# HashUnit1.net
KiCad netlist of a schematic drawn in Altium Designer
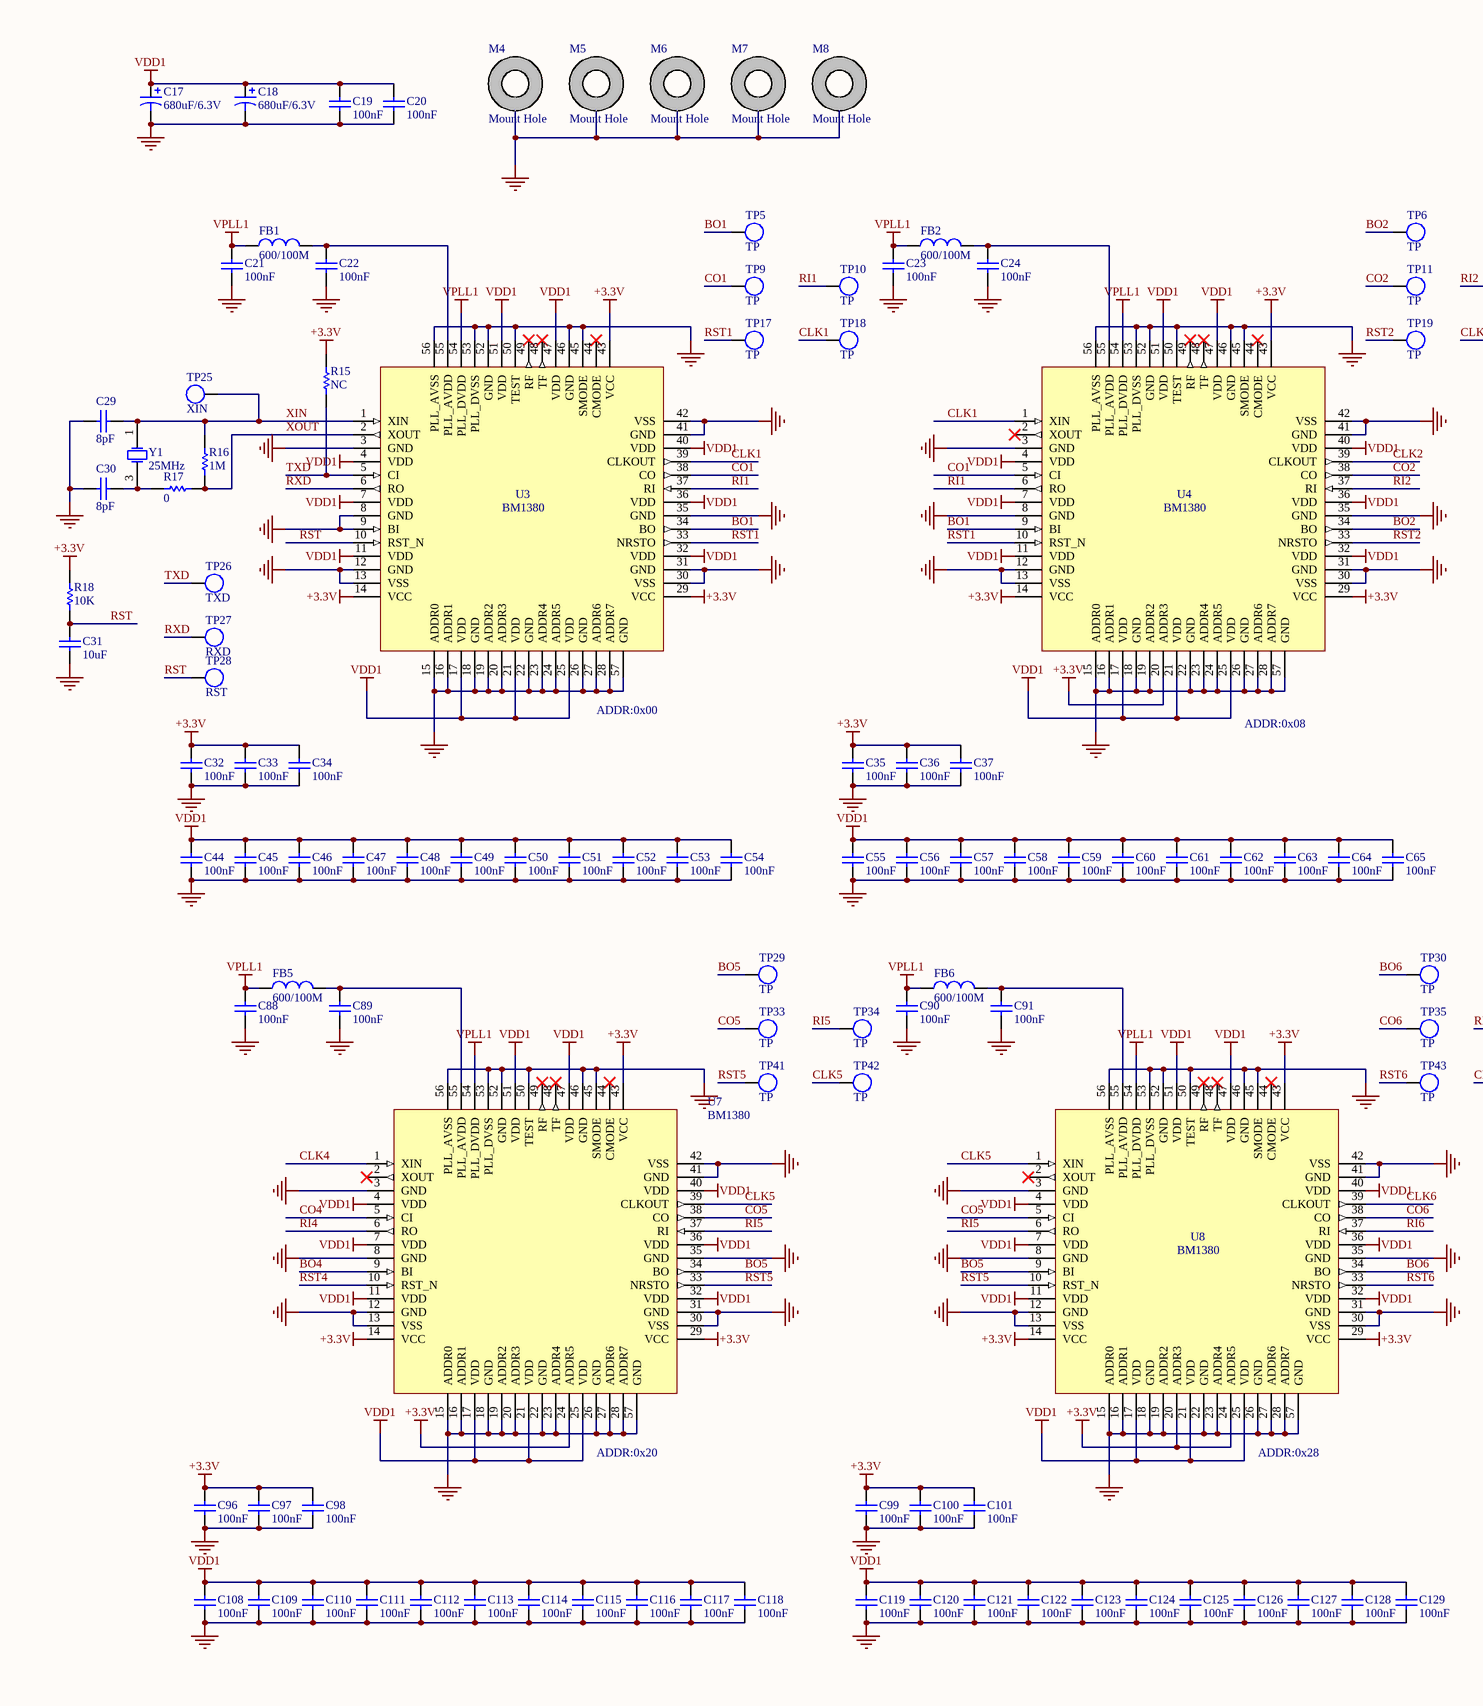
[diagram p0: HashUnit1.SchDoc, left]
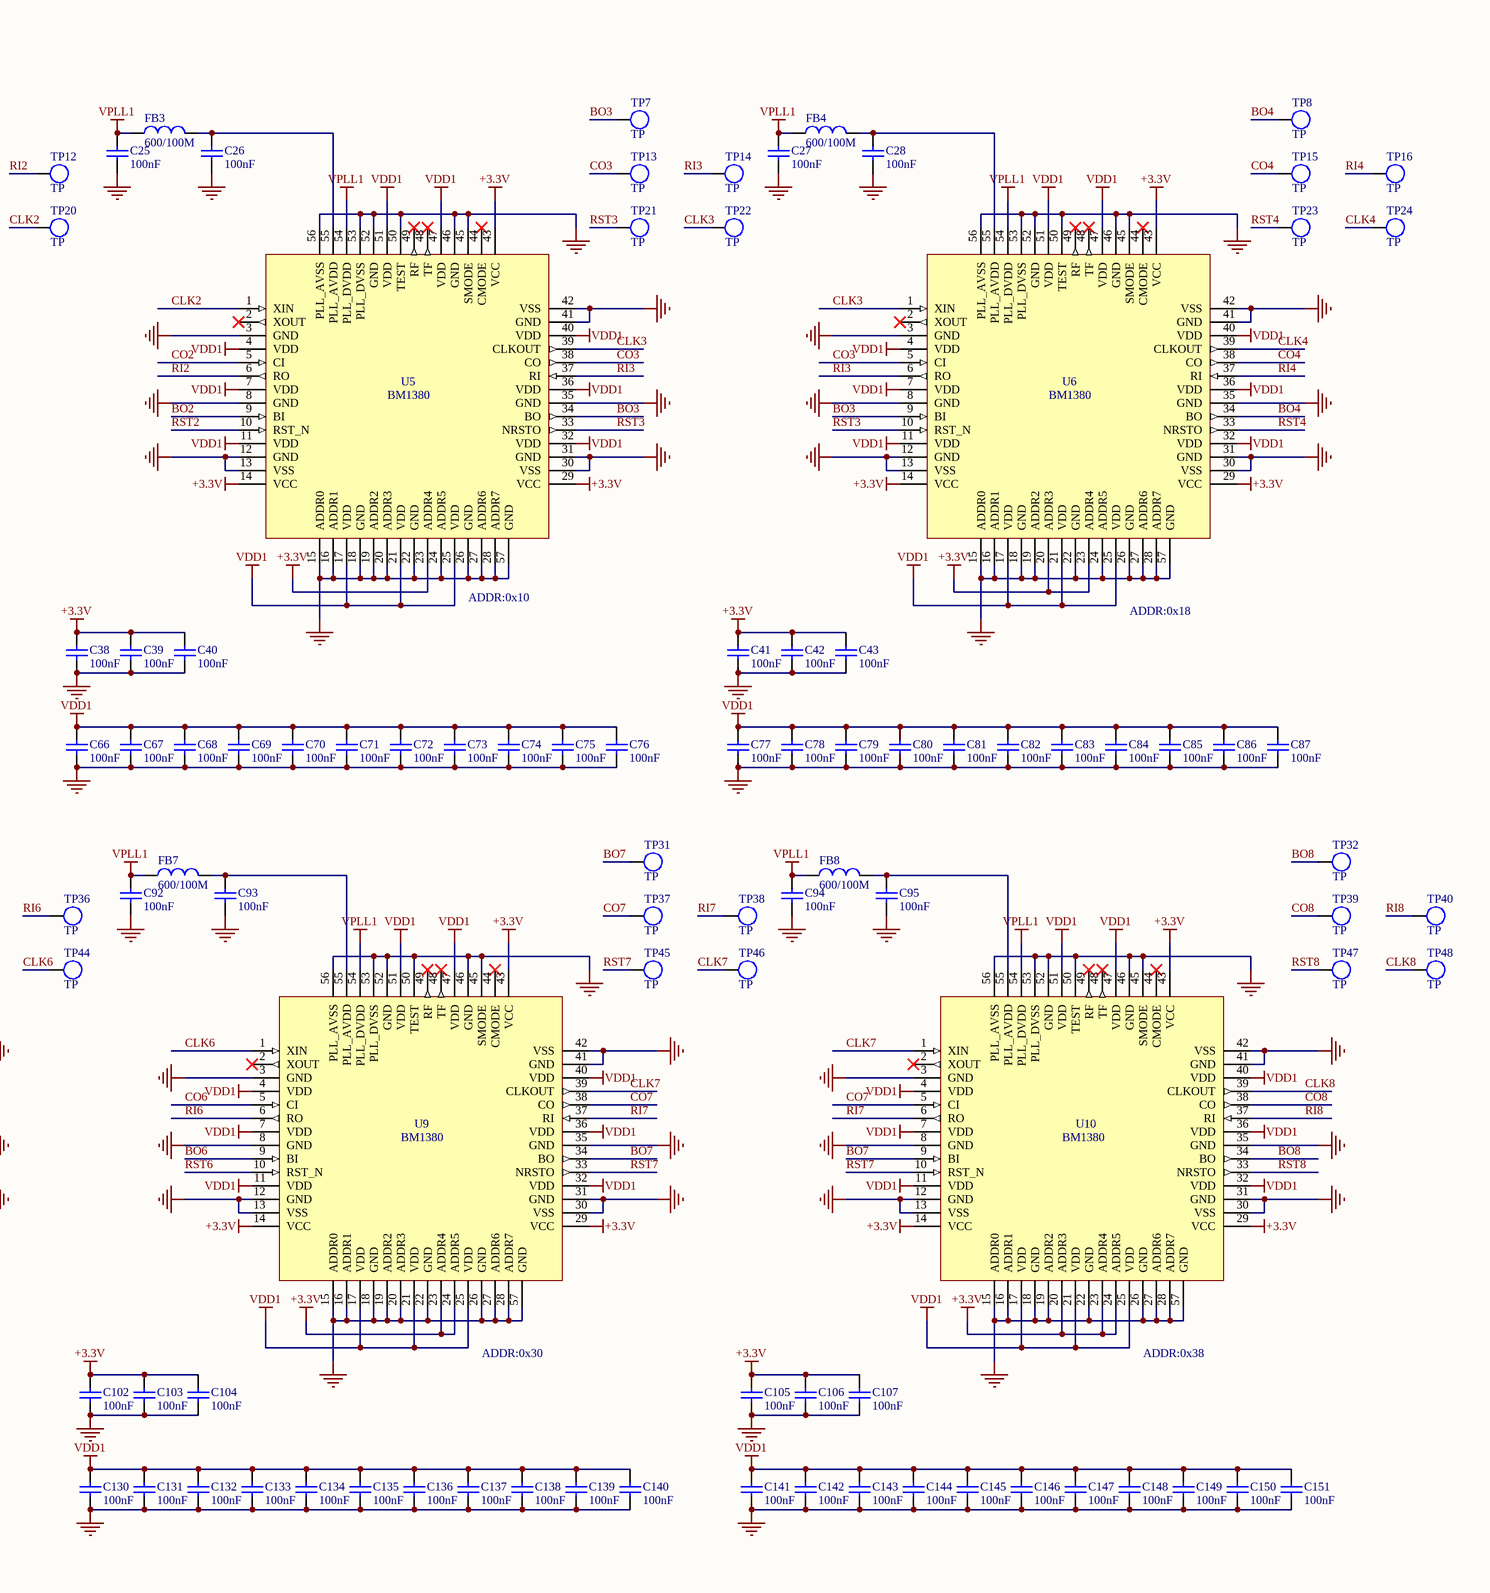
[diagram p1: HashUnit1.SchDoc, right]

(export (version "E")
  (design (tool "Eeschema 10.0.6"))
  (components
    (comp (ref "C17")
      (value "680uF/6.3V")
      (footprint "D")
      (description "Solid Tantalum Chip Capacitor, T492 Series - CWR11 Style Per Mil-PRF-55365/8")
      (fields (field (name "PUBLISHER") "Altium Limited"))
      (libsource (lib "KEMET Chip Capacitor") (part "T492C"))
    )
    (comp (ref "C18")
      (value "680uF/6.3V")
      (footprint "D")
      (description "Solid Tantalum Chip Capacitor, T492 Series - CWR11 Style Per Mil-PRF-55365/8")
      (fields (field (name "PUBLISHER") "Altium Limited"))
      (libsource (lib "KEMET Chip Capacitor") (part "T492C"))
    )
    (comp (ref "C19")
      (value "100nF")
      (footprint "CC0603(1608)")
      (description "Capacitor (Semiconductor SIM Model)")
      (fields (field (name "PUBLISHER") "Altium Limited"))
      (libsource (lib "Miscellaneous Devices") (part "Cap Semi"))
    )
    (comp (ref "C20")
      (value "100nF")
      (footprint "CC0603(1608)")
      (description "Capacitor (Semiconductor SIM Model)")
      (fields (field (name "PUBLISHER") "Altium Limited"))
      (libsource (lib "Miscellaneous Devices") (part "Cap Semi"))
    )
    (comp (ref "C21")
      (value "100nF")
      (footprint "CC0603(1608)")
      (description "Capacitor")
      (fields (field (name "PUBLISHER") "Altium Limited"))
      (libsource (lib "BitMain_Miner_1") (part "Cap"))
    )
    (comp (ref "C22")
      (value "100nF")
      (footprint "CC0603(1608)")
      (description "Capacitor")
      (fields (field (name "PUBLISHER") "Altium Limited"))
      (libsource (lib "BitMain_Miner_1") (part "Cap"))
    )
    (comp (ref "C23")
      (value "100nF")
      (footprint "CC0603(1608)")
      (description "Capacitor")
      (fields (field (name "PUBLISHER") "Altium Limited"))
      (libsource (lib "BitMain_Miner_1") (part "Cap"))
    )
    (comp (ref "C24")
      (value "100nF")
      (footprint "CC0603(1608)")
      (description "Capacitor")
      (fields (field (name "PUBLISHER") "Altium Limited"))
      (libsource (lib "BitMain_Miner_1") (part "Cap"))
    )
    (comp (ref "C25")
      (value "100nF")
      (footprint "CC0603(1608)")
      (description "Capacitor")
      (fields (field (name "PUBLISHER") "Altium Limited"))
      (libsource (lib "BitMain_Miner_1") (part "Cap"))
    )
    (comp (ref "C26")
      (value "100nF")
      (footprint "CC0603(1608)")
      (description "Capacitor")
      (fields (field (name "PUBLISHER") "Altium Limited"))
      (libsource (lib "BitMain_Miner_1") (part "Cap"))
    )
    (comp (ref "C27")
      (value "100nF")
      (footprint "CC0603(1608)")
      (description "Capacitor")
      (fields (field (name "PUBLISHER") "Altium Limited"))
      (libsource (lib "BitMain_Miner_1") (part "Cap"))
    )
    (comp (ref "C28")
      (value "100nF")
      (footprint "CC0603(1608)")
      (description "Capacitor")
      (fields (field (name "PUBLISHER") "Altium Limited"))
      (libsource (lib "BitMain_Miner_1") (part "Cap"))
    )
    (comp (ref "C29")
      (value "8pF")
      (footprint "CC0603(1608)")
      (description "Capacitor")
      (fields (field (name "PUBLISHER") "Altium Limited"))
      (libsource (lib "BitMain_Miner_1") (part "Cap"))
    )
    (comp (ref "C30")
      (value "8pF")
      (footprint "CC0603(1608)")
      (description "Capacitor")
      (fields (field (name "PUBLISHER") "Altium Limited"))
      (libsource (lib "BitMain_Miner_1") (part "Cap"))
    )
    (comp (ref "C31")
      (value "10uF")
      (footprint "CC0603(1608)")
      (description "Capacitor")
      (fields (field (name "PUBLISHER") "Altium Limited"))
      (libsource (lib "BitMain_Miner_1") (part "Cap"))
    )
    (comp (ref "C32")
      (value "100nF")
      (footprint "CC0603(1608)")
      (description "Capacitor")
      (fields (field (name "PUBLISHER") "Altium Limited"))
      (libsource (lib "BitMain_Miner_1") (part "Cap"))
    )
    (comp (ref "C33")
      (value "100nF")
      (footprint "CC0603(1608)")
      (description "Capacitor")
      (fields (field (name "PUBLISHER") "Altium Limited"))
      (libsource (lib "BitMain_Miner_1") (part "Cap"))
    )
    (comp (ref "C34")
      (value "100nF")
      (footprint "CC0603(1608)")
      (description "Capacitor")
      (fields (field (name "PUBLISHER") "Altium Limited"))
      (libsource (lib "BitMain_Miner_1") (part "Cap"))
    )
    (comp (ref "C35")
      (value "100nF")
      (footprint "CC0603(1608)")
      (description "Capacitor")
      (fields (field (name "PUBLISHER") "Altium Limited"))
      (libsource (lib "BitMain_Miner_1") (part "Cap"))
    )
    (comp (ref "C36")
      (value "100nF")
      (footprint "CC0603(1608)")
      (description "Capacitor")
      (fields (field (name "PUBLISHER") "Altium Limited"))
      (libsource (lib "BitMain_Miner_1") (part "Cap"))
    )
    (comp (ref "C37")
      (value "100nF")
      (footprint "CC0603(1608)")
      (description "Capacitor")
      (fields (field (name "PUBLISHER") "Altium Limited"))
      (libsource (lib "BitMain_Miner_1") (part "Cap"))
    )
    (comp (ref "C38")
      (value "100nF")
      (footprint "CC0603(1608)")
      (description "Capacitor")
      (fields (field (name "PUBLISHER") "Altium Limited"))
      (libsource (lib "BitMain_Miner_1") (part "Cap"))
    )
    (comp (ref "C39")
      (value "100nF")
      (footprint "CC0603(1608)")
      (description "Capacitor")
      (fields (field (name "PUBLISHER") "Altium Limited"))
      (libsource (lib "BitMain_Miner_1") (part "Cap"))
    )
    (comp (ref "C40")
      (value "100nF")
      (footprint "CC0603(1608)")
      (description "Capacitor")
      (fields (field (name "PUBLISHER") "Altium Limited"))
      (libsource (lib "BitMain_Miner_1") (part "Cap"))
    )
    (comp (ref "C41")
      (value "100nF")
      (footprint "CC0603(1608)")
      (description "Capacitor")
      (fields (field (name "PUBLISHER") "Altium Limited"))
      (libsource (lib "BitMain_Miner_1") (part "Cap"))
    )
    (comp (ref "C42")
      (value "100nF")
      (footprint "CC0603(1608)")
      (description "Capacitor")
      (fields (field (name "PUBLISHER") "Altium Limited"))
      (libsource (lib "BitMain_Miner_1") (part "Cap"))
    )
    (comp (ref "C43")
      (value "100nF")
      (footprint "CC0603(1608)")
      (description "Capacitor")
      (fields (field (name "PUBLISHER") "Altium Limited"))
      (libsource (lib "BitMain_Miner_1") (part "Cap"))
    )
    (comp (ref "C44")
      (value "100nF")
      (footprint "CC0603(1608)")
      (description "Capacitor")
      (fields (field (name "PUBLISHER") "Altium Limited"))
      (libsource (lib "BitMain_Miner_1") (part "Cap"))
    )
    (comp (ref "C45")
      (value "100nF")
      (footprint "CC0603(1608)")
      (description "Capacitor")
      (fields (field (name "PUBLISHER") "Altium Limited"))
      (libsource (lib "BitMain_Miner_1") (part "Cap"))
    )
    (comp (ref "C46")
      (value "100nF")
      (footprint "CC0603(1608)")
      (description "Capacitor")
      (fields (field (name "PUBLISHER") "Altium Limited"))
      (libsource (lib "BitMain_Miner_1") (part "Cap"))
    )
    (comp (ref "C47")
      (value "100nF")
      (footprint "CC0603(1608)")
      (description "Capacitor")
      (fields (field (name "PUBLISHER") "Altium Limited"))
      (libsource (lib "BitMain_Miner_1") (part "Cap"))
    )
    (comp (ref "C48")
      (value "100nF")
      (footprint "CC0603(1608)")
      (description "Capacitor")
      (fields (field (name "PUBLISHER") "Altium Limited"))
      (libsource (lib "BitMain_Miner_1") (part "Cap"))
    )
    (comp (ref "C49")
      (value "100nF")
      (footprint "CC0603(1608)")
      (description "Capacitor")
      (fields (field (name "PUBLISHER") "Altium Limited"))
      (libsource (lib "BitMain_Miner_1") (part "Cap"))
    )
    (comp (ref "C50")
      (value "100nF")
      (footprint "CC0603(1608)")
      (description "Capacitor")
      (fields (field (name "PUBLISHER") "Altium Limited"))
      (libsource (lib "BitMain_Miner_1") (part "Cap"))
    )
    (comp (ref "C51")
      (value "100nF")
      (footprint "CC0603(1608)")
      (description "Capacitor")
      (fields (field (name "PUBLISHER") "Altium Limited"))
      (libsource (lib "BitMain_Miner_1") (part "Cap"))
    )
    (comp (ref "C52")
      (value "100nF")
      (footprint "CC0603(1608)")
      (description "Capacitor")
      (fields (field (name "PUBLISHER") "Altium Limited"))
      (libsource (lib "BitMain_Miner_1") (part "Cap"))
    )
    (comp (ref "C53")
      (value "100nF")
      (footprint "CC0603(1608)")
      (description "Capacitor")
      (fields (field (name "PUBLISHER") "Altium Limited"))
      (libsource (lib "BitMain_Miner_1") (part "Cap"))
    )
    (comp (ref "C54")
      (value "100nF")
      (footprint "CC0603(1608)")
      (description "Capacitor")
      (fields (field (name "PUBLISHER") "Altium Limited"))
      (libsource (lib "BitMain_Miner_1") (part "Cap"))
    )
    (comp (ref "C55")
      (value "100nF")
      (footprint "CC0603(1608)")
      (description "Capacitor")
      (fields (field (name "PUBLISHER") "Altium Limited"))
      (libsource (lib "BitMain_Miner_1") (part "Cap"))
    )
    (comp (ref "C56")
      (value "100nF")
      (footprint "CC0603(1608)")
      (description "Capacitor")
      (fields (field (name "PUBLISHER") "Altium Limited"))
      (libsource (lib "BitMain_Miner_1") (part "Cap"))
    )
    (comp (ref "C57")
      (value "100nF")
      (footprint "CC0603(1608)")
      (description "Capacitor")
      (fields (field (name "PUBLISHER") "Altium Limited"))
      (libsource (lib "BitMain_Miner_1") (part "Cap"))
    )
    (comp (ref "C58")
      (value "100nF")
      (footprint "CC0603(1608)")
      (description "Capacitor")
      (fields (field (name "PUBLISHER") "Altium Limited"))
      (libsource (lib "BitMain_Miner_1") (part "Cap"))
    )
    (comp (ref "C59")
      (value "100nF")
      (footprint "CC0603(1608)")
      (description "Capacitor")
      (fields (field (name "PUBLISHER") "Altium Limited"))
      (libsource (lib "BitMain_Miner_1") (part "Cap"))
    )
    (comp (ref "C60")
      (value "100nF")
      (footprint "CC0603(1608)")
      (description "Capacitor")
      (fields (field (name "PUBLISHER") "Altium Limited"))
      (libsource (lib "BitMain_Miner_1") (part "Cap"))
    )
    (comp (ref "C61")
      (value "100nF")
      (footprint "CC0603(1608)")
      (description "Capacitor")
      (fields (field (name "PUBLISHER") "Altium Limited"))
      (libsource (lib "BitMain_Miner_1") (part "Cap"))
    )
    (comp (ref "C62")
      (value "100nF")
      (footprint "CC0603(1608)")
      (description "Capacitor")
      (fields (field (name "PUBLISHER") "Altium Limited"))
      (libsource (lib "BitMain_Miner_1") (part "Cap"))
    )
    (comp (ref "C63")
      (value "100nF")
      (footprint "CC0603(1608)")
      (description "Capacitor")
      (fields (field (name "PUBLISHER") "Altium Limited"))
      (libsource (lib "BitMain_Miner_1") (part "Cap"))
    )
    (comp (ref "C64")
      (value "100nF")
      (footprint "CC0603(1608)")
      (description "Capacitor")
      (fields (field (name "PUBLISHER") "Altium Limited"))
      (libsource (lib "BitMain_Miner_1") (part "Cap"))
    )
    (comp (ref "C65")
      (value "100nF")
      (footprint "CC0603(1608)")
      (description "Capacitor")
      (fields (field (name "PUBLISHER") "Altium Limited"))
      (libsource (lib "BitMain_Miner_1") (part "Cap"))
    )
    (comp (ref "C66")
      (value "100nF")
      (footprint "CC0603(1608)")
      (description "Capacitor")
      (fields (field (name "PUBLISHER") "Altium Limited"))
      (libsource (lib "BitMain_Miner_1") (part "Cap"))
    )
    (comp (ref "C67")
      (value "100nF")
      (footprint "CC0603(1608)")
      (description "Capacitor")
      (fields (field (name "PUBLISHER") "Altium Limited"))
      (libsource (lib "BitMain_Miner_1") (part "Cap"))
    )
    (comp (ref "C68")
      (value "100nF")
      (footprint "CC0603(1608)")
      (description "Capacitor")
      (fields (field (name "PUBLISHER") "Altium Limited"))
      (libsource (lib "BitMain_Miner_1") (part "Cap"))
    )
    (comp (ref "C69")
      (value "100nF")
      (footprint "CC0603(1608)")
      (description "Capacitor")
      (fields (field (name "PUBLISHER") "Altium Limited"))
      (libsource (lib "BitMain_Miner_1") (part "Cap"))
    )
    (comp (ref "C70")
      (value "100nF")
      (footprint "CC0603(1608)")
      (description "Capacitor")
      (fields (field (name "PUBLISHER") "Altium Limited"))
      (libsource (lib "BitMain_Miner_1") (part "Cap"))
    )
    (comp (ref "C71")
      (value "100nF")
      (footprint "CC0603(1608)")
      (description "Capacitor")
      (fields (field (name "PUBLISHER") "Altium Limited"))
      (libsource (lib "BitMain_Miner_1") (part "Cap"))
    )
    (comp (ref "C72")
      (value "100nF")
      (footprint "CC0603(1608)")
      (description "Capacitor")
      (fields (field (name "PUBLISHER") "Altium Limited"))
      (libsource (lib "BitMain_Miner_1") (part "Cap"))
    )
    (comp (ref "C73")
      (value "100nF")
      (footprint "CC0603(1608)")
      (description "Capacitor")
      (fields (field (name "PUBLISHER") "Altium Limited"))
      (libsource (lib "BitMain_Miner_1") (part "Cap"))
    )
    (comp (ref "C74")
      (value "100nF")
      (footprint "CC0603(1608)")
      (description "Capacitor")
      (fields (field (name "PUBLISHER") "Altium Limited"))
      (libsource (lib "BitMain_Miner_1") (part "Cap"))
    )
    (comp (ref "C75")
      (value "100nF")
      (footprint "CC0603(1608)")
      (description "Capacitor")
      (fields (field (name "PUBLISHER") "Altium Limited"))
      (libsource (lib "BitMain_Miner_1") (part "Cap"))
    )
    (comp (ref "C76")
      (value "100nF")
      (footprint "CC0603(1608)")
      (description "Capacitor")
      (fields (field (name "PUBLISHER") "Altium Limited"))
      (libsource (lib "BitMain_Miner_1") (part "Cap"))
    )
    (comp (ref "C77")
      (value "100nF")
      (footprint "CC0603(1608)")
      (description "Capacitor")
      (fields (field (name "PUBLISHER") "Altium Limited"))
      (libsource (lib "BitMain_Miner_1") (part "Cap"))
    )
    (comp (ref "C78")
      (value "100nF")
      (footprint "CC0603(1608)")
      (description "Capacitor")
      (fields (field (name "PUBLISHER") "Altium Limited"))
      (libsource (lib "BitMain_Miner_1") (part "Cap"))
    )
    (comp (ref "C79")
      (value "100nF")
      (footprint "CC0603(1608)")
      (description "Capacitor")
      (fields (field (name "PUBLISHER") "Altium Limited"))
      (libsource (lib "BitMain_Miner_1") (part "Cap"))
    )
    (comp (ref "C80")
      (value "100nF")
      (footprint "CC0603(1608)")
      (description "Capacitor")
      (fields (field (name "PUBLISHER") "Altium Limited"))
      (libsource (lib "BitMain_Miner_1") (part "Cap"))
    )
    (comp (ref "C81")
      (value "100nF")
      (footprint "CC0603(1608)")
      (description "Capacitor")
      (fields (field (name "PUBLISHER") "Altium Limited"))
      (libsource (lib "BitMain_Miner_1") (part "Cap"))
    )
    (comp (ref "C82")
      (value "100nF")
      (footprint "CC0603(1608)")
      (description "Capacitor")
      (fields (field (name "PUBLISHER") "Altium Limited"))
      (libsource (lib "BitMain_Miner_1") (part "Cap"))
    )
    (comp (ref "C83")
      (value "100nF")
      (footprint "CC0603(1608)")
      (description "Capacitor")
      (fields (field (name "PUBLISHER") "Altium Limited"))
      (libsource (lib "BitMain_Miner_1") (part "Cap"))
    )
    (comp (ref "C84")
      (value "100nF")
      (footprint "CC0603(1608)")
      (description "Capacitor")
      (fields (field (name "PUBLISHER") "Altium Limited"))
      (libsource (lib "BitMain_Miner_1") (part "Cap"))
    )
    (comp (ref "C85")
      (value "100nF")
      (footprint "CC0603(1608)")
      (description "Capacitor")
      (fields (field (name "PUBLISHER") "Altium Limited"))
      (libsource (lib "BitMain_Miner_1") (part "Cap"))
    )
    (comp (ref "C86")
      (value "100nF")
      (footprint "CC0603(1608)")
      (description "Capacitor")
      (fields (field (name "PUBLISHER") "Altium Limited"))
      (libsource (lib "BitMain_Miner_1") (part "Cap"))
    )
    (comp (ref "C87")
      (value "100nF")
      (footprint "CC0603(1608)")
      (description "Capacitor")
      (fields (field (name "PUBLISHER") "Altium Limited"))
      (libsource (lib "BitMain_Miner_1") (part "Cap"))
    )
    (comp (ref "C88")
      (value "100nF")
      (footprint "CC0603(1608)")
      (description "Capacitor")
      (fields (field (name "PUBLISHER") "Altium Limited"))
      (libsource (lib "BitMain_Miner_1") (part "Cap"))
    )
    (comp (ref "C89")
      (value "100nF")
      (footprint "CC0603(1608)")
      (description "Capacitor")
      (fields (field (name "PUBLISHER") "Altium Limited"))
      (libsource (lib "BitMain_Miner_1") (part "Cap"))
    )
    (comp (ref "C90")
      (value "100nF")
      (footprint "CC0603(1608)")
      (description "Capacitor")
      (fields (field (name "PUBLISHER") "Altium Limited"))
      (libsource (lib "BitMain_Miner_1") (part "Cap"))
    )
    (comp (ref "C91")
      (value "100nF")
      (footprint "CC0603(1608)")
      (description "Capacitor")
      (fields (field (name "PUBLISHER") "Altium Limited"))
      (libsource (lib "BitMain_Miner_1") (part "Cap"))
    )
    (comp (ref "C92")
      (value "100nF")
      (footprint "CC0603(1608)")
      (description "Capacitor")
      (fields (field (name "PUBLISHER") "Altium Limited"))
      (libsource (lib "BitMain_Miner_1") (part "Cap"))
    )
    (comp (ref "C93")
      (value "100nF")
      (footprint "CC0603(1608)")
      (description "Capacitor")
      (fields (field (name "PUBLISHER") "Altium Limited"))
      (libsource (lib "BitMain_Miner_1") (part "Cap"))
    )
    (comp (ref "C94")
      (value "100nF")
      (footprint "CC0603(1608)")
      (description "Capacitor")
      (fields (field (name "PUBLISHER") "Altium Limited"))
      (libsource (lib "BitMain_Miner_1") (part "Cap"))
    )
    (comp (ref "C95")
      (value "100nF")
      (footprint "CC0603(1608)")
      (description "Capacitor")
      (fields (field (name "PUBLISHER") "Altium Limited"))
      (libsource (lib "BitMain_Miner_1") (part "Cap"))
    )
    (comp (ref "C96")
      (value "100nF")
      (footprint "CC0603(1608)")
      (description "Capacitor")
      (fields (field (name "PUBLISHER") "Altium Limited"))
      (libsource (lib "BitMain_Miner_1") (part "Cap"))
    )
    (comp (ref "C97")
      (value "100nF")
      (footprint "CC0603(1608)")
      (description "Capacitor")
      (fields (field (name "PUBLISHER") "Altium Limited"))
      (libsource (lib "BitMain_Miner_1") (part "Cap"))
    )
    (comp (ref "C98")
      (value "100nF")
      (footprint "CC0603(1608)")
      (description "Capacitor")
      (fields (field (name "PUBLISHER") "Altium Limited"))
      (libsource (lib "BitMain_Miner_1") (part "Cap"))
    )
    (comp (ref "C99")
      (value "100nF")
      (footprint "CC0603(1608)")
      (description "Capacitor")
      (fields (field (name "PUBLISHER") "Altium Limited"))
      (libsource (lib "BitMain_Miner_1") (part "Cap"))
    )
    (comp (ref "C100")
      (value "100nF")
      (footprint "CC0603(1608)")
      (description "Capacitor")
      (fields (field (name "PUBLISHER") "Altium Limited"))
      (libsource (lib "BitMain_Miner_1") (part "Cap"))
    )
    (comp (ref "C101")
      (value "100nF")
      (footprint "CC0603(1608)")
      (description "Capacitor")
      (fields (field (name "PUBLISHER") "Altium Limited"))
      (libsource (lib "BitMain_Miner_1") (part "Cap"))
    )
    (comp (ref "C102")
      (value "100nF")
      (footprint "CC0603(1608)")
      (description "Capacitor")
      (fields (field (name "PUBLISHER") "Altium Limited"))
      (libsource (lib "BitMain_Miner_1") (part "Cap"))
    )
    (comp (ref "C103")
      (value "100nF")
      (footprint "CC0603(1608)")
      (description "Capacitor")
      (fields (field (name "PUBLISHER") "Altium Limited"))
      (libsource (lib "BitMain_Miner_1") (part "Cap"))
    )
    (comp (ref "C104")
      (value "100nF")
      (footprint "CC0603(1608)")
      (description "Capacitor")
      (fields (field (name "PUBLISHER") "Altium Limited"))
      (libsource (lib "BitMain_Miner_1") (part "Cap"))
    )
    (comp (ref "C105")
      (value "100nF")
      (footprint "CC0603(1608)")
      (description "Capacitor")
      (fields (field (name "PUBLISHER") "Altium Limited"))
      (libsource (lib "BitMain_Miner_1") (part "Cap"))
    )
    (comp (ref "C106")
      (value "100nF")
      (footprint "CC0603(1608)")
      (description "Capacitor")
      (fields (field (name "PUBLISHER") "Altium Limited"))
      (libsource (lib "BitMain_Miner_1") (part "Cap"))
    )
    (comp (ref "C107")
      (value "100nF")
      (footprint "CC0603(1608)")
      (description "Capacitor")
      (fields (field (name "PUBLISHER") "Altium Limited"))
      (libsource (lib "BitMain_Miner_1") (part "Cap"))
    )
    (comp (ref "C108")
      (value "100nF")
      (footprint "CC0603(1608)")
      (description "Capacitor")
      (fields (field (name "PUBLISHER") "Altium Limited"))
      (libsource (lib "BitMain_Miner_1") (part "Cap"))
    )
    (comp (ref "C109")
      (value "100nF")
      (footprint "CC0603(1608)")
      (description "Capacitor")
      (fields (field (name "PUBLISHER") "Altium Limited"))
      (libsource (lib "BitMain_Miner_1") (part "Cap"))
    )
    (comp (ref "C110")
      (value "100nF")
      (footprint "CC0603(1608)")
      (description "Capacitor")
      (fields (field (name "PUBLISHER") "Altium Limited"))
      (libsource (lib "BitMain_Miner_1") (part "Cap"))
    )
    (comp (ref "C111")
      (value "100nF")
      (footprint "CC0603(1608)")
      (description "Capacitor")
      (fields (field (name "PUBLISHER") "Altium Limited"))
      (libsource (lib "BitMain_Miner_1") (part "Cap"))
    )
    (comp (ref "C112")
      (value "100nF")
      (footprint "CC0603(1608)")
      (description "Capacitor")
      (fields (field (name "PUBLISHER") "Altium Limited"))
      (libsource (lib "BitMain_Miner_1") (part "Cap"))
    )
    (comp (ref "C113")
      (value "100nF")
      (footprint "CC0603(1608)")
      (description "Capacitor")
      (fields (field (name "PUBLISHER") "Altium Limited"))
      (libsource (lib "BitMain_Miner_1") (part "Cap"))
    )
    (comp (ref "C114")
      (value "100nF")
      (footprint "CC0603(1608)")
      (description "Capacitor")
      (fields (field (name "PUBLISHER") "Altium Limited"))
      (libsource (lib "BitMain_Miner_1") (part "Cap"))
    )
    (comp (ref "C115")
      (value "100nF")
      (footprint "CC0603(1608)")
      (description "Capacitor")
      (fields (field (name "PUBLISHER") "Altium Limited"))
      (libsource (lib "BitMain_Miner_1") (part "Cap"))
    )
    (comp (ref "C116")
      (value "100nF")
      (footprint "CC0603(1608)")
      (description "Capacitor")
      (fields (field (name "PUBLISHER") "Altium Limited"))
      (libsource (lib "BitMain_Miner_1") (part "Cap"))
    )
    (comp (ref "C117")
      (value "100nF")
      (footprint "CC0603(1608)")
      (description "Capacitor")
      (fields (field (name "PUBLISHER") "Altium Limited"))
      (libsource (lib "BitMain_Miner_1") (part "Cap"))
    )
    (comp (ref "C118")
      (value "100nF")
      (footprint "CC0603(1608)")
      (description "Capacitor")
      (fields (field (name "PUBLISHER") "Altium Limited"))
      (libsource (lib "BitMain_Miner_1") (part "Cap"))
    )
    (comp (ref "C119")
      (value "100nF")
      (footprint "CC0603(1608)")
      (description "Capacitor")
      (fields (field (name "PUBLISHER") "Altium Limited"))
      (libsource (lib "BitMain_Miner_1") (part "Cap"))
    )
    (comp (ref "C120")
      (value "100nF")
      (footprint "CC0603(1608)")
      (description "Capacitor")
      (fields (field (name "PUBLISHER") "Altium Limited"))
      (libsource (lib "BitMain_Miner_1") (part "Cap"))
    )
    (comp (ref "C121")
      (value "100nF")
      (footprint "CC0603(1608)")
      (description "Capacitor")
      (fields (field (name "PUBLISHER") "Altium Limited"))
      (libsource (lib "BitMain_Miner_1") (part "Cap"))
    )
    (comp (ref "C122")
      (value "100nF")
      (footprint "CC0603(1608)")
      (description "Capacitor")
      (fields (field (name "PUBLISHER") "Altium Limited"))
      (libsource (lib "BitMain_Miner_1") (part "Cap"))
    )
    (comp (ref "C123")
      (value "100nF")
      (footprint "CC0603(1608)")
      (description "Capacitor")
      (fields (field (name "PUBLISHER") "Altium Limited"))
      (libsource (lib "BitMain_Miner_1") (part "Cap"))
    )
    (comp (ref "C124")
      (value "100nF")
      (footprint "CC0603(1608)")
      (description "Capacitor")
      (fields (field (name "PUBLISHER") "Altium Limited"))
      (libsource (lib "BitMain_Miner_1") (part "Cap"))
    )
    (comp (ref "C125")
      (value "100nF")
      (footprint "CC0603(1608)")
      (description "Capacitor")
      (fields (field (name "PUBLISHER") "Altium Limited"))
      (libsource (lib "BitMain_Miner_1") (part "Cap"))
    )
    (comp (ref "C126")
      (value "100nF")
      (footprint "CC0603(1608)")
      (description "Capacitor")
      (fields (field (name "PUBLISHER") "Altium Limited"))
      (libsource (lib "BitMain_Miner_1") (part "Cap"))
    )
    (comp (ref "C127")
      (value "100nF")
      (footprint "CC0603(1608)")
      (description "Capacitor")
      (fields (field (name "PUBLISHER") "Altium Limited"))
      (libsource (lib "BitMain_Miner_1") (part "Cap"))
    )
    (comp (ref "C128")
      (value "100nF")
      (footprint "CC0603(1608)")
      (description "Capacitor")
      (fields (field (name "PUBLISHER") "Altium Limited"))
      (libsource (lib "BitMain_Miner_1") (part "Cap"))
    )
    (comp (ref "C129")
      (value "100nF")
      (footprint "CC0603(1608)")
      (description "Capacitor")
      (fields (field (name "PUBLISHER") "Altium Limited"))
      (libsource (lib "BitMain_Miner_1") (part "Cap"))
    )
    (comp (ref "C130")
      (value "100nF")
      (footprint "CC0603(1608)")
      (description "Capacitor")
      (fields (field (name "PUBLISHER") "Altium Limited"))
      (libsource (lib "BitMain_Miner_1") (part "Cap"))
    )
    (comp (ref "C131")
      (value "100nF")
      (footprint "CC0603(1608)")
      (description "Capacitor")
      (fields (field (name "PUBLISHER") "Altium Limited"))
      (libsource (lib "BitMain_Miner_1") (part "Cap"))
    )
    (comp (ref "C132")
      (value "100nF")
      (footprint "CC0603(1608)")
      (description "Capacitor")
      (fields (field (name "PUBLISHER") "Altium Limited"))
      (libsource (lib "BitMain_Miner_1") (part "Cap"))
    )
    (comp (ref "C133")
      (value "100nF")
      (footprint "CC0603(1608)")
      (description "Capacitor")
      (fields (field (name "PUBLISHER") "Altium Limited"))
      (libsource (lib "BitMain_Miner_1") (part "Cap"))
    )
    (comp (ref "C134")
      (value "100nF")
      (footprint "CC0603(1608)")
      (description "Capacitor")
      (fields (field (name "PUBLISHER") "Altium Limited"))
      (libsource (lib "BitMain_Miner_1") (part "Cap"))
    )
    (comp (ref "C135")
      (value "100nF")
      (footprint "CC0603(1608)")
      (description "Capacitor")
      (fields (field (name "PUBLISHER") "Altium Limited"))
      (libsource (lib "BitMain_Miner_1") (part "Cap"))
    )
    (comp (ref "C136")
      (value "100nF")
      (footprint "CC0603(1608)")
      (description "Capacitor")
      (fields (field (name "PUBLISHER") "Altium Limited"))
      (libsource (lib "BitMain_Miner_1") (part "Cap"))
    )
    (comp (ref "C137")
      (value "100nF")
      (footprint "CC0603(1608)")
      (description "Capacitor")
      (fields (field (name "PUBLISHER") "Altium Limited"))
      (libsource (lib "BitMain_Miner_1") (part "Cap"))
    )
    (comp (ref "C138")
      (value "100nF")
      (footprint "CC0603(1608)")
      (description "Capacitor")
      (fields (field (name "PUBLISHER") "Altium Limited"))
      (libsource (lib "BitMain_Miner_1") (part "Cap"))
    )
    (comp (ref "C139")
      (value "100nF")
      (footprint "CC0603(1608)")
      (description "Capacitor")
      (fields (field (name "PUBLISHER") "Altium Limited"))
      (libsource (lib "BitMain_Miner_1") (part "Cap"))
    )
    (comp (ref "C140")
      (value "100nF")
      (footprint "CC0603(1608)")
      (description "Capacitor")
      (fields (field (name "PUBLISHER") "Altium Limited"))
      (libsource (lib "BitMain_Miner_1") (part "Cap"))
    )
    (comp (ref "C141")
      (value "100nF")
      (footprint "CC0603(1608)")
      (description "Capacitor")
      (fields (field (name "PUBLISHER") "Altium Limited"))
      (libsource (lib "BitMain_Miner_1") (part "Cap"))
    )
    (comp (ref "C142")
      (value "100nF")
      (footprint "CC0603(1608)")
      (description "Capacitor")
      (fields (field (name "PUBLISHER") "Altium Limited"))
      (libsource (lib "BitMain_Miner_1") (part "Cap"))
    )
    (comp (ref "C143")
      (value "100nF")
      (footprint "CC0603(1608)")
      (description "Capacitor")
      (fields (field (name "PUBLISHER") "Altium Limited"))
      (libsource (lib "BitMain_Miner_1") (part "Cap"))
    )
    (comp (ref "C144")
      (value "100nF")
      (footprint "CC0603(1608)")
      (description "Capacitor")
      (fields (field (name "PUBLISHER") "Altium Limited"))
      (libsource (lib "BitMain_Miner_1") (part "Cap"))
    )
    (comp (ref "C145")
      (value "100nF")
      (footprint "CC0603(1608)")
      (description "Capacitor")
      (fields (field (name "PUBLISHER") "Altium Limited"))
      (libsource (lib "BitMain_Miner_1") (part "Cap"))
    )
    (comp (ref "C146")
      (value "100nF")
      (footprint "CC0603(1608)")
      (description "Capacitor")
      (fields (field (name "PUBLISHER") "Altium Limited"))
      (libsource (lib "BitMain_Miner_1") (part "Cap"))
    )
    (comp (ref "C147")
      (value "100nF")
      (footprint "CC0603(1608)")
      (description "Capacitor")
      (fields (field (name "PUBLISHER") "Altium Limited"))
      (libsource (lib "BitMain_Miner_1") (part "Cap"))
    )
    (comp (ref "C148")
      (value "100nF")
      (footprint "CC0603(1608)")
      (description "Capacitor")
      (fields (field (name "PUBLISHER") "Altium Limited"))
      (libsource (lib "BitMain_Miner_1") (part "Cap"))
    )
    (comp (ref "C149")
      (value "100nF")
      (footprint "CC0603(1608)")
      (description "Capacitor")
      (fields (field (name "PUBLISHER") "Altium Limited"))
      (libsource (lib "BitMain_Miner_1") (part "Cap"))
    )
    (comp (ref "C150")
      (value "100nF")
      (footprint "CC0603(1608)")
      (description "Capacitor")
      (fields (field (name "PUBLISHER") "Altium Limited"))
      (libsource (lib "BitMain_Miner_1") (part "Cap"))
    )
    (comp (ref "C151")
      (value "100nF")
      (footprint "CC0603(1608)")
      (description "Capacitor")
      (fields (field (name "PUBLISHER") "Altium Limited"))
      (libsource (lib "BitMain_Miner_1") (part "Cap"))
    )
    (comp (ref "FB1")
      (value "600/100M")
      (footprint "FB0603(1608)")
      (description "Inductor")
      (fields (field (name "PUBLISHER") "Altium Limited"))
      (libsource (lib "BitMain_Miner_1") (part "FB"))
    )
    (comp (ref "FB2")
      (value "600/100M")
      (footprint "FB0603(1608)")
      (description "Inductor")
      (fields (field (name "PUBLISHER") "Altium Limited"))
      (libsource (lib "BitMain_Miner_1") (part "FB"))
    )
    (comp (ref "FB3")
      (value "600/100M")
      (footprint "FB0603(1608)")
      (description "Inductor")
      (fields (field (name "PUBLISHER") "Altium Limited"))
      (libsource (lib "BitMain_Miner_1") (part "FB"))
    )
    (comp (ref "FB4")
      (value "600/100M")
      (footprint "FB0603(1608)")
      (description "Inductor")
      (fields (field (name "PUBLISHER") "Altium Limited"))
      (libsource (lib "BitMain_Miner_1") (part "FB"))
    )
    (comp (ref "FB5")
      (value "600/100M")
      (footprint "FB0603(1608)")
      (description "Inductor")
      (fields (field (name "PUBLISHER") "Altium Limited"))
      (libsource (lib "BitMain_Miner_1") (part "FB"))
    )
    (comp (ref "FB6")
      (value "600/100M")
      (footprint "FB0603(1608)")
      (description "Inductor")
      (fields (field (name "PUBLISHER") "Altium Limited"))
      (libsource (lib "BitMain_Miner_1") (part "FB"))
    )
    (comp (ref "FB7")
      (value "600/100M")
      (footprint "FB0603(1608)")
      (description "Inductor")
      (fields (field (name "PUBLISHER") "Altium Limited"))
      (libsource (lib "BitMain_Miner_1") (part "FB"))
    )
    (comp (ref "FB8")
      (value "600/100M")
      (footprint "FB0603(1608)")
      (description "Inductor")
      (fields (field (name "PUBLISHER") "Altium Limited"))
      (libsource (lib "BitMain_Miner_1") (part "FB"))
    )
    (comp (ref "M4") (value "Mount Hole") (footprint "MHOLE2") (libsource (lib "S6_2") (part "M_Hole")))
    (comp (ref "M5") (value "Mount Hole") (footprint "MHOLE2") (libsource (lib "S6_2") (part "M_Hole")))
    (comp (ref "M6") (value "Mount Hole") (footprint "MHOLE2") (libsource (lib "S6_2") (part "M_Hole")))
    (comp (ref "M7") (value "Mount Hole") (footprint "MHOLE2") (libsource (lib "S6_2") (part "M_Hole")))
    (comp (ref "M8") (value "Mount Hole") (footprint "MHOLE2") (libsource (lib "S6_2") (part "M_Hole")))
    (comp (ref "R15")
      (value "NC")
      (footprint "RR0603(1608)")
      (description "Resistor")
      (fields (field (name "PUBLISHER") "Altium Limited"))
      (libsource (lib "BitMain_Miner_1") (part "Res1"))
    )
    (comp (ref "R16")
      (value "1M")
      (footprint "RR0603(1608)")
      (description "Resistor")
      (fields (field (name "PUBLISHER") "Altium Limited"))
      (libsource (lib "BitMain_Miner_1") (part "Res1"))
    )
    (comp (ref "R17")
      (value "0")
      (footprint "RR0603(1608)")
      (description "Resistor")
      (fields (field (name "PUBLISHER") "Altium Limited"))
      (libsource (lib "BitMain_Miner_1") (part "Res1"))
    )
    (comp (ref "R18")
      (value "10K")
      (footprint "RR0603(1608)")
      (description "Resistor")
      (fields (field (name "PUBLISHER") "Altium Limited"))
      (libsource (lib "BitMain_Miner_1") (part "Res1"))
    )
    (comp (ref "TP5")
      (value "TP")
      (footprint "TP_SMD")
      (description "Test Point")
      (libsource (lib "BitMain_Miner_1") (part "TP"))
    )
    (comp (ref "TP6")
      (value "TP")
      (footprint "TP_SMD")
      (description "Test Point")
      (libsource (lib "BitMain_Miner_1") (part "TP"))
    )
    (comp (ref "TP7")
      (value "TP")
      (footprint "TP_SMD")
      (description "Test Point")
      (libsource (lib "BitMain_Miner_1") (part "TP"))
    )
    (comp (ref "TP8")
      (value "TP")
      (footprint "TP_SMD")
      (description "Test Point")
      (libsource (lib "BitMain_Miner_1") (part "TP"))
    )
    (comp (ref "TP9")
      (value "TP")
      (footprint "TP_SMD")
      (description "Test Point")
      (libsource (lib "BitMain_Miner_1") (part "TP"))
    )
    (comp (ref "TP10")
      (value "TP")
      (footprint "TP_SMD")
      (description "Test Point")
      (libsource (lib "BitMain_Miner_1") (part "TP"))
    )
    (comp (ref "TP11")
      (value "TP")
      (footprint "TP_SMD")
      (description "Test Point")
      (libsource (lib "BitMain_Miner_1") (part "TP"))
    )
    (comp (ref "TP12")
      (value "TP")
      (footprint "TP_SMD")
      (description "Test Point")
      (libsource (lib "BitMain_Miner_1") (part "TP"))
    )
    (comp (ref "TP13")
      (value "TP")
      (footprint "TP_SMD")
      (description "Test Point")
      (libsource (lib "BitMain_Miner_1") (part "TP"))
    )
    (comp (ref "TP14")
      (value "TP")
      (footprint "TP_SMD")
      (description "Test Point")
      (libsource (lib "BitMain_Miner_1") (part "TP"))
    )
    (comp (ref "TP15")
      (value "TP")
      (footprint "TP_SMD")
      (description "Test Point")
      (libsource (lib "BitMain_Miner_1") (part "TP"))
    )
    (comp (ref "TP16")
      (value "TP")
      (footprint "TP_SMD")
      (description "Test Point")
      (libsource (lib "BitMain_Miner_1") (part "TP"))
    )
    (comp (ref "TP17")
      (value "TP")
      (footprint "TP_SMD")
      (description "Test Point")
      (libsource (lib "BitMain_Miner_1") (part "TP"))
    )
    (comp (ref "TP18")
      (value "TP")
      (footprint "TP_SMD")
      (description "Test Point")
      (libsource (lib "BitMain_Miner_1") (part "TP"))
    )
    (comp (ref "TP19")
      (value "TP")
      (footprint "TP_SMD")
      (description "Test Point")
      (libsource (lib "BitMain_Miner_1") (part "TP"))
    )
    (comp (ref "TP20")
      (value "TP")
      (footprint "TP_SMD")
      (description "Test Point")
      (libsource (lib "BitMain_Miner_1") (part "TP"))
    )
    (comp (ref "TP21")
      (value "TP")
      (footprint "TP_SMD")
      (description "Test Point")
      (libsource (lib "BitMain_Miner_1") (part "TP"))
    )
    (comp (ref "TP22")
      (value "TP")
      (footprint "TP_SMD")
      (description "Test Point")
      (libsource (lib "BitMain_Miner_1") (part "TP"))
    )
    (comp (ref "TP23")
      (value "TP")
      (footprint "TP_SMD")
      (description "Test Point")
      (libsource (lib "BitMain_Miner_1") (part "TP"))
    )
    (comp (ref "TP24")
      (value "TP")
      (footprint "TP_SMD")
      (description "Test Point")
      (libsource (lib "BitMain_Miner_1") (part "TP"))
    )
    (comp (ref "TP25")
      (value "XIN")
      (footprint "TP_SMD")
      (description "Test Point")
      (fields (field (name "Comment") "TP"))
      (libsource (lib "BitMain_Miner_1") (part "TP"))
    )
    (comp (ref "TP26")
      (value "TXD")
      (footprint "TP_SMD")
      (description "Test Point")
      (fields (field (name "Comment") "TP"))
      (libsource (lib "BitMain_Miner_1") (part "TP"))
    )
    (comp (ref "TP27")
      (value "RXD")
      (footprint "TP_SMD")
      (description "Test Point")
      (fields (field (name "Comment") "TP"))
      (libsource (lib "BitMain_Miner_1") (part "TP"))
    )
    (comp (ref "TP28")
      (value "RST")
      (footprint "TP_SMD")
      (description "Test Point")
      (fields (field (name "Comment") "TP"))
      (libsource (lib "BitMain_Miner_1") (part "TP"))
    )
    (comp (ref "TP29")
      (value "TP")
      (footprint "TP_SMD")
      (description "Test Point")
      (libsource (lib "BitMain_Miner_1") (part "TP"))
    )
    (comp (ref "TP30")
      (value "TP")
      (footprint "TP_SMD")
      (description "Test Point")
      (libsource (lib "BitMain_Miner_1") (part "TP"))
    )
    (comp (ref "TP31")
      (value "TP")
      (footprint "TP_SMD")
      (description "Test Point")
      (libsource (lib "BitMain_Miner_1") (part "TP"))
    )
    (comp (ref "TP32")
      (value "TP")
      (footprint "TP_SMD")
      (description "Test Point")
      (libsource (lib "BitMain_Miner_1") (part "TP"))
    )
    (comp (ref "TP33")
      (value "TP")
      (footprint "TP_SMD")
      (description "Test Point")
      (libsource (lib "BitMain_Miner_1") (part "TP"))
    )
    (comp (ref "TP34")
      (value "TP")
      (footprint "TP_SMD")
      (description "Test Point")
      (libsource (lib "BitMain_Miner_1") (part "TP"))
    )
    (comp (ref "TP35")
      (value "TP")
      (footprint "TP_SMD")
      (description "Test Point")
      (libsource (lib "BitMain_Miner_1") (part "TP"))
    )
    (comp (ref "TP36")
      (value "TP")
      (footprint "TP_SMD")
      (description "Test Point")
      (libsource (lib "BitMain_Miner_1") (part "TP"))
    )
    (comp (ref "TP37")
      (value "TP")
      (footprint "TP_SMD")
      (description "Test Point")
      (libsource (lib "BitMain_Miner_1") (part "TP"))
    )
    (comp (ref "TP38")
      (value "TP")
      (footprint "TP_SMD")
      (description "Test Point")
      (libsource (lib "BitMain_Miner_1") (part "TP"))
    )
    (comp (ref "TP39")
      (value "TP")
      (footprint "TP_SMD")
      (description "Test Point")
      (libsource (lib "BitMain_Miner_1") (part "TP"))
    )
    (comp (ref "TP40")
      (value "TP")
      (footprint "TP_SMD")
      (description "Test Point")
      (libsource (lib "BitMain_Miner_1") (part "TP"))
    )
    (comp (ref "TP41")
      (value "TP")
      (footprint "TP_SMD")
      (description "Test Point")
      (libsource (lib "BitMain_Miner_1") (part "TP"))
    )
    (comp (ref "TP42")
      (value "TP")
      (footprint "TP_SMD")
      (description "Test Point")
      (libsource (lib "BitMain_Miner_1") (part "TP"))
    )
    (comp (ref "TP43")
      (value "TP")
      (footprint "TP_SMD")
      (description "Test Point")
      (libsource (lib "BitMain_Miner_1") (part "TP"))
    )
    (comp (ref "TP44")
      (value "TP")
      (footprint "TP_SMD")
      (description "Test Point")
      (libsource (lib "BitMain_Miner_1") (part "TP"))
    )
    (comp (ref "TP45")
      (value "TP")
      (footprint "TP_SMD")
      (description "Test Point")
      (libsource (lib "BitMain_Miner_1") (part "TP"))
    )
    (comp (ref "TP46")
      (value "TP")
      (footprint "TP_SMD")
      (description "Test Point")
      (libsource (lib "BitMain_Miner_1") (part "TP"))
    )
    (comp (ref "TP47")
      (value "TP")
      (footprint "TP_SMD")
      (description "Test Point")
      (libsource (lib "BitMain_Miner_1") (part "TP"))
    )
    (comp (ref "TP48")
      (value "TP")
      (footprint "TP_SMD")
      (description "Test Point")
      (libsource (lib "BitMain_Miner_1") (part "TP"))
    )
    (comp (ref "U3") (value "BM1380") (footprint "QFN56") (libsource (lib "ANT_Miner_V1.3") (part "BM1380")))
    (comp (ref "U4") (value "BM1380") (footprint "QFN56") (libsource (lib "ANT_Miner_V1.3") (part "BM1380")))
    (comp (ref "U5") (value "BM1380") (footprint "QFN56") (libsource (lib "ANT_Miner_V1.3") (part "BM1380")))
    (comp (ref "U6") (value "BM1380") (footprint "QFN56") (libsource (lib "ANT_Miner_V1.3") (part "BM1380")))
    (comp (ref "U7") (value "BM1380") (footprint "QFN56") (libsource (lib "ANT_Miner_V1.3") (part "BM1380")))
    (comp (ref "U8") (value "BM1380") (footprint "QFN56") (libsource (lib "ANT_Miner_V1.3") (part "BM1380")))
    (comp (ref "U9") (value "BM1380") (footprint "QFN56") (libsource (lib "ANT_Miner_V1.3") (part "BM1380")))
    (comp (ref "U10") (value "BM1380") (footprint "QFN56") (libsource (lib "ANT_Miner_V1.3") (part "BM1380")))
    (comp (ref "Y1")
      (value "25MHz")
      (footprint "SMX2")
      (description "Crystal Oscillator")
      (fields (field (name "PUBLISHER") "Altium Limited"))
      (libsource (lib "BitMain_Miner_1") (part "XTAL"))
    )
  )
  (nets
    (net (code "1") (name "+3.3V") (class "Default")
      (node (ref "C100") (pin "2") (pinfunction "2_2") (pintype "passive"))
      (node (ref "C101") (pin "2") (pinfunction "2_2") (pintype "passive"))
      (node (ref "C102") (pin "2") (pinfunction "2_2") (pintype "passive"))
      (node (ref "C103") (pin "2") (pinfunction "2_2") (pintype "passive"))
      (node (ref "C104") (pin "2") (pinfunction "2_2") (pintype "passive"))
      (node (ref "C105") (pin "2") (pinfunction "2_2") (pintype "passive"))
      (node (ref "C106") (pin "2") (pinfunction "2_2") (pintype "passive"))
      (node (ref "C107") (pin "2") (pinfunction "2_2") (pintype "passive"))
      (node (ref "C32") (pin "2") (pinfunction "2_2") (pintype "passive"))
      (node (ref "C33") (pin "2") (pinfunction "2_2") (pintype "passive"))
      (node (ref "C34") (pin "2") (pinfunction "2_2") (pintype "passive"))
      (node (ref "C35") (pin "2") (pinfunction "2_2") (pintype "passive"))
      (node (ref "C36") (pin "2") (pinfunction "2_2") (pintype "passive"))
      (node (ref "C37") (pin "2") (pinfunction "2_2") (pintype "passive"))
      (node (ref "C38") (pin "2") (pinfunction "2_2") (pintype "passive"))
      (node (ref "C39") (pin "2") (pinfunction "2_2") (pintype "passive"))
      (node (ref "C40") (pin "2") (pinfunction "2_2") (pintype "passive"))
      (node (ref "C41") (pin "2") (pinfunction "2_2") (pintype "passive"))
      (node (ref "C42") (pin "2") (pinfunction "2_2") (pintype "passive"))
      (node (ref "C43") (pin "2") (pinfunction "2_2") (pintype "passive"))
      (node (ref "C96") (pin "2") (pinfunction "2_2") (pintype "passive"))
      (node (ref "C97") (pin "2") (pinfunction "2_2") (pintype "passive"))
      (node (ref "C98") (pin "2") (pinfunction "2_2") (pintype "passive"))
      (node (ref "C99") (pin "2") (pinfunction "2_2") (pintype "passive"))
      (node (ref "R15") (pin "1") (pinfunction "1_1") (pintype "passive"))
      (node (ref "R18") (pin "2") (pinfunction "2_2") (pintype "passive"))
      (node (ref "U10") (pin "14") (pinfunction "VCC_14") (pintype "power_in"))
      (node (ref "U10") (pin "20") (pinfunction "ADDR3_20") (pintype "passive"))
      (node (ref "U10") (pin "23") (pinfunction "ADDR4_23") (pintype "passive"))
      (node (ref "U10") (pin "24") (pinfunction "ADDR5_24") (pintype "passive"))
      (node (ref "U10") (pin "29") (pinfunction "VCC_29") (pintype "power_in"))
      (node (ref "U10") (pin "43") (pinfunction "VCC_43") (pintype "power_in"))
      (node (ref "U3") (pin "14") (pinfunction "VCC_14") (pintype "power_in"))
      (node (ref "U3") (pin "29") (pinfunction "VCC_29") (pintype "power_in"))
      (node (ref "U3") (pin "43") (pinfunction "VCC_43") (pintype "power_in"))
      (node (ref "U4") (pin "14") (pinfunction "VCC_14") (pintype "power_in"))
      (node (ref "U4") (pin "20") (pinfunction "ADDR3_20") (pintype "passive"))
      (node (ref "U4") (pin "29") (pinfunction "VCC_29") (pintype "power_in"))
      (node (ref "U4") (pin "43") (pinfunction "VCC_43") (pintype "power_in"))
      (node (ref "U5") (pin "14") (pinfunction "VCC_14") (pintype "power_in"))
      (node (ref "U5") (pin "23") (pinfunction "ADDR4_23") (pintype "passive"))
      (node (ref "U5") (pin "29") (pinfunction "VCC_29") (pintype "power_in"))
      (node (ref "U5") (pin "43") (pinfunction "VCC_43") (pintype "power_in"))
      (node (ref "U6") (pin "14") (pinfunction "VCC_14") (pintype "power_in"))
      (node (ref "U6") (pin "20") (pinfunction "ADDR3_20") (pintype "passive"))
      (node (ref "U6") (pin "23") (pinfunction "ADDR4_23") (pintype "passive"))
      (node (ref "U6") (pin "29") (pinfunction "VCC_29") (pintype "power_in"))
      (node (ref "U6") (pin "43") (pinfunction "VCC_43") (pintype "power_in"))
      (node (ref "U7") (pin "14") (pinfunction "VCC_14") (pintype "power_in"))
      (node (ref "U7") (pin "24") (pinfunction "ADDR5_24") (pintype "passive"))
      (node (ref "U7") (pin "29") (pinfunction "VCC_29") (pintype "power_in"))
      (node (ref "U7") (pin "43") (pinfunction "VCC_43") (pintype "power_in"))
      (node (ref "U8") (pin "14") (pinfunction "VCC_14") (pintype "power_in"))
      (node (ref "U8") (pin "20") (pinfunction "ADDR3_20") (pintype "passive"))
      (node (ref "U8") (pin "24") (pinfunction "ADDR5_24") (pintype "passive"))
      (node (ref "U8") (pin "29") (pinfunction "VCC_29") (pintype "power_in"))
      (node (ref "U8") (pin "43") (pinfunction "VCC_43") (pintype "power_in"))
      (node (ref "U9") (pin "14") (pinfunction "VCC_14") (pintype "power_in"))
      (node (ref "U9") (pin "23") (pinfunction "ADDR4_23") (pintype "passive"))
      (node (ref "U9") (pin "24") (pinfunction "ADDR5_24") (pintype "passive"))
      (node (ref "U9") (pin "29") (pinfunction "VCC_29") (pintype "power_in"))
      (node (ref "U9") (pin "43") (pinfunction "VCC_43") (pintype "power_in"))
    )
    (net (code "2") (name "/BO1") (class "Default")
      (node (ref "TP5") (pin "1") (pinfunction "1_1") (pintype "passive"))
      (node (ref "U3") (pin "34") (pinfunction "BO_34") (pintype "output"))
      (node (ref "U4") (pin "9") (pinfunction "BI_9") (pintype "input"))
    )
    (net (code "3") (name "/BO2") (class "Default")
      (node (ref "TP6") (pin "1") (pinfunction "1_1") (pintype "passive"))
      (node (ref "U4") (pin "34") (pinfunction "BO_34") (pintype "output"))
      (node (ref "U5") (pin "9") (pinfunction "BI_9") (pintype "input"))
    )
    (net (code "4") (name "/BO3") (class "Default")
      (node (ref "TP7") (pin "1") (pinfunction "1_1") (pintype "passive"))
      (node (ref "U5") (pin "34") (pinfunction "BO_34") (pintype "output"))
      (node (ref "U6") (pin "9") (pinfunction "BI_9") (pintype "input"))
    )
    (net (code "5") (name "/BO4") (class "Default")
      (node (ref "TP8") (pin "1") (pinfunction "1_1") (pintype "passive"))
      (node (ref "U6") (pin "34") (pinfunction "BO_34") (pintype "output"))
      (node (ref "U7") (pin "9") (pinfunction "BI_9") (pintype "input"))
    )
    (net (code "6") (name "/BO5") (class "Default")
      (node (ref "TP29") (pin "1") (pinfunction "1_1") (pintype "passive"))
      (node (ref "U7") (pin "34") (pinfunction "BO_34") (pintype "output"))
      (node (ref "U8") (pin "9") (pinfunction "BI_9") (pintype "input"))
    )
    (net (code "7") (name "/BO6") (class "Default")
      (node (ref "TP30") (pin "1") (pinfunction "1_1") (pintype "passive"))
      (node (ref "U8") (pin "34") (pinfunction "BO_34") (pintype "output"))
      (node (ref "U9") (pin "9") (pinfunction "BI_9") (pintype "input"))
    )
    (net (code "8") (name "/BO7") (class "Default")
      (node (ref "TP31") (pin "1") (pinfunction "1_1") (pintype "passive"))
      (node (ref "U10") (pin "9") (pinfunction "BI_9") (pintype "input"))
      (node (ref "U9") (pin "34") (pinfunction "BO_34") (pintype "output"))
    )
    (net (code "9") (name "/BO8") (class "Default")
      (node (ref "TP32") (pin "1") (pinfunction "1_1") (pintype "passive"))
      (node (ref "U10") (pin "34") (pinfunction "BO_34") (pintype "output"))
    )
    (net (code "10") (name "/CLK1") (class "Default")
      (node (ref "TP18") (pin "1") (pinfunction "1_1") (pintype "passive"))
      (node (ref "U3") (pin "39") (pinfunction "CLKOUT_39") (pintype "output"))
      (node (ref "U4") (pin "1") (pinfunction "XIN_1") (pintype "input"))
    )
    (net (code "11") (name "/CLK2") (class "Default")
      (node (ref "TP20") (pin "1") (pinfunction "1_1") (pintype "passive"))
      (node (ref "U4") (pin "39") (pinfunction "CLKOUT_39") (pintype "output"))
      (node (ref "U5") (pin "1") (pinfunction "XIN_1") (pintype "input"))
    )
    (net (code "12") (name "/CLK3") (class "Default")
      (node (ref "TP22") (pin "1") (pinfunction "1_1") (pintype "passive"))
      (node (ref "U5") (pin "39") (pinfunction "CLKOUT_39") (pintype "output"))
      (node (ref "U6") (pin "1") (pinfunction "XIN_1") (pintype "input"))
    )
    (net (code "13") (name "/CLK4") (class "Default")
      (node (ref "TP24") (pin "1") (pinfunction "1_1") (pintype "passive"))
      (node (ref "U6") (pin "39") (pinfunction "CLKOUT_39") (pintype "output"))
      (node (ref "U7") (pin "1") (pinfunction "XIN_1") (pintype "input"))
    )
    (net (code "14") (name "/CLK5") (class "Default")
      (node (ref "TP42") (pin "1") (pinfunction "1_1") (pintype "passive"))
      (node (ref "U7") (pin "39") (pinfunction "CLKOUT_39") (pintype "output"))
      (node (ref "U8") (pin "1") (pinfunction "XIN_1") (pintype "input"))
    )
    (net (code "15") (name "/CLK6") (class "Default")
      (node (ref "TP44") (pin "1") (pinfunction "1_1") (pintype "passive"))
      (node (ref "U8") (pin "39") (pinfunction "CLKOUT_39") (pintype "output"))
      (node (ref "U9") (pin "1") (pinfunction "XIN_1") (pintype "input"))
    )
    (net (code "16") (name "/CLK7") (class "Default")
      (node (ref "TP46") (pin "1") (pinfunction "1_1") (pintype "passive"))
      (node (ref "U10") (pin "1") (pinfunction "XIN_1") (pintype "input"))
      (node (ref "U9") (pin "39") (pinfunction "CLKOUT_39") (pintype "output"))
    )
    (net (code "17") (name "/CLK8") (class "Default")
      (node (ref "TP48") (pin "1") (pinfunction "1_1") (pintype "passive"))
      (node (ref "U10") (pin "39") (pinfunction "CLKOUT_39") (pintype "output"))
    )
    (net (code "18") (name "/CO1") (class "Default")
      (node (ref "TP9") (pin "1") (pinfunction "1_1") (pintype "passive"))
      (node (ref "U3") (pin "38") (pinfunction "CO_38") (pintype "output"))
      (node (ref "U4") (pin "5") (pinfunction "CI_5") (pintype "input"))
    )
    (net (code "19") (name "/CO2") (class "Default")
      (node (ref "TP11") (pin "1") (pinfunction "1_1") (pintype "passive"))
      (node (ref "U4") (pin "38") (pinfunction "CO_38") (pintype "output"))
      (node (ref "U5") (pin "5") (pinfunction "CI_5") (pintype "input"))
    )
    (net (code "20") (name "/CO3") (class "Default")
      (node (ref "TP13") (pin "1") (pinfunction "1_1") (pintype "passive"))
      (node (ref "U5") (pin "38") (pinfunction "CO_38") (pintype "output"))
      (node (ref "U6") (pin "5") (pinfunction "CI_5") (pintype "input"))
    )
    (net (code "21") (name "/CO4") (class "Default")
      (node (ref "TP15") (pin "1") (pinfunction "1_1") (pintype "passive"))
      (node (ref "U6") (pin "38") (pinfunction "CO_38") (pintype "output"))
      (node (ref "U7") (pin "5") (pinfunction "CI_5") (pintype "input"))
    )
    (net (code "22") (name "/CO5") (class "Default")
      (node (ref "TP33") (pin "1") (pinfunction "1_1") (pintype "passive"))
      (node (ref "U7") (pin "38") (pinfunction "CO_38") (pintype "output"))
      (node (ref "U8") (pin "5") (pinfunction "CI_5") (pintype "input"))
    )
    (net (code "23") (name "/CO6") (class "Default")
      (node (ref "TP35") (pin "1") (pinfunction "1_1") (pintype "passive"))
      (node (ref "U8") (pin "38") (pinfunction "CO_38") (pintype "output"))
      (node (ref "U9") (pin "5") (pinfunction "CI_5") (pintype "input"))
    )
    (net (code "24") (name "/CO7") (class "Default")
      (node (ref "TP37") (pin "1") (pinfunction "1_1") (pintype "passive"))
      (node (ref "U10") (pin "5") (pinfunction "CI_5") (pintype "input"))
      (node (ref "U9") (pin "38") (pinfunction "CO_38") (pintype "output"))
    )
    (net (code "25") (name "/CO8") (class "Default")
      (node (ref "TP39") (pin "1") (pinfunction "1_1") (pintype "passive"))
      (node (ref "U10") (pin "38") (pinfunction "CO_38") (pintype "output"))
    )
    (net (code "26") (name "/RI1") (class "Default")
      (node (ref "TP10") (pin "1") (pinfunction "1_1") (pintype "passive"))
      (node (ref "U3") (pin "37") (pinfunction "RI_37") (pintype "input"))
      (node (ref "U4") (pin "6") (pinfunction "RO_6") (pintype "output"))
    )
    (net (code "27") (name "/RI2") (class "Default")
      (node (ref "TP12") (pin "1") (pinfunction "1_1") (pintype "passive"))
      (node (ref "U4") (pin "37") (pinfunction "RI_37") (pintype "input"))
      (node (ref "U5") (pin "6") (pinfunction "RO_6") (pintype "output"))
    )
    (net (code "28") (name "/RI3") (class "Default")
      (node (ref "TP14") (pin "1") (pinfunction "1_1") (pintype "passive"))
      (node (ref "U5") (pin "37") (pinfunction "RI_37") (pintype "input"))
      (node (ref "U6") (pin "6") (pinfunction "RO_6") (pintype "output"))
    )
    (net (code "29") (name "/RI4") (class "Default")
      (node (ref "TP16") (pin "1") (pinfunction "1_1") (pintype "passive"))
      (node (ref "U6") (pin "37") (pinfunction "RI_37") (pintype "input"))
      (node (ref "U7") (pin "6") (pinfunction "RO_6") (pintype "output"))
    )
    (net (code "30") (name "/RI5") (class "Default")
      (node (ref "TP34") (pin "1") (pinfunction "1_1") (pintype "passive"))
      (node (ref "U7") (pin "37") (pinfunction "RI_37") (pintype "input"))
      (node (ref "U8") (pin "6") (pinfunction "RO_6") (pintype "output"))
    )
    (net (code "31") (name "/RI6") (class "Default")
      (node (ref "TP36") (pin "1") (pinfunction "1_1") (pintype "passive"))
      (node (ref "U8") (pin "37") (pinfunction "RI_37") (pintype "input"))
      (node (ref "U9") (pin "6") (pinfunction "RO_6") (pintype "output"))
    )
    (net (code "32") (name "/RI7") (class "Default")
      (node (ref "TP38") (pin "1") (pinfunction "1_1") (pintype "passive"))
      (node (ref "U10") (pin "6") (pinfunction "RO_6") (pintype "output"))
      (node (ref "U9") (pin "37") (pinfunction "RI_37") (pintype "input"))
    )
    (net (code "33") (name "/RI8") (class "Default")
      (node (ref "TP40") (pin "1") (pinfunction "1_1") (pintype "passive"))
      (node (ref "U10") (pin "37") (pinfunction "RI_37") (pintype "input"))
    )
    (net (code "34") (name "/RST") (class "Default")
      (node (ref "C31") (pin "1") (pinfunction "1_1") (pintype "passive"))
      (node (ref "R18") (pin "1") (pinfunction "1_1") (pintype "passive"))
      (node (ref "TP28") (pin "1") (pinfunction "1_1") (pintype "passive"))
      (node (ref "U3") (pin "10") (pinfunction "RST_N_10") (pintype "input"))
    )
    (net (code "35") (name "/RST1") (class "Default")
      (node (ref "TP17") (pin "1") (pinfunction "1_1") (pintype "passive"))
      (node (ref "U3") (pin "33") (pinfunction "NRSTO_33") (pintype "output"))
      (node (ref "U4") (pin "10") (pinfunction "RST_N_10") (pintype "input"))
    )
    (net (code "36") (name "/RST2") (class "Default")
      (node (ref "TP19") (pin "1") (pinfunction "1_1") (pintype "passive"))
      (node (ref "U4") (pin "33") (pinfunction "NRSTO_33") (pintype "output"))
      (node (ref "U5") (pin "10") (pinfunction "RST_N_10") (pintype "input"))
    )
    (net (code "37") (name "/RST3") (class "Default")
      (node (ref "TP21") (pin "1") (pinfunction "1_1") (pintype "passive"))
      (node (ref "U5") (pin "33") (pinfunction "NRSTO_33") (pintype "output"))
      (node (ref "U6") (pin "10") (pinfunction "RST_N_10") (pintype "input"))
    )
    (net (code "38") (name "/RST4") (class "Default")
      (node (ref "TP23") (pin "1") (pinfunction "1_1") (pintype "passive"))
      (node (ref "U6") (pin "33") (pinfunction "NRSTO_33") (pintype "output"))
      (node (ref "U7") (pin "10") (pinfunction "RST_N_10") (pintype "input"))
    )
    (net (code "39") (name "/RST5") (class "Default")
      (node (ref "TP41") (pin "1") (pinfunction "1_1") (pintype "passive"))
      (node (ref "U7") (pin "33") (pinfunction "NRSTO_33") (pintype "output"))
      (node (ref "U8") (pin "10") (pinfunction "RST_N_10") (pintype "input"))
    )
    (net (code "40") (name "/RST6") (class "Default")
      (node (ref "TP43") (pin "1") (pinfunction "1_1") (pintype "passive"))
      (node (ref "U8") (pin "33") (pinfunction "NRSTO_33") (pintype "output"))
      (node (ref "U9") (pin "10") (pinfunction "RST_N_10") (pintype "input"))
    )
    (net (code "41") (name "/RST7") (class "Default")
      (node (ref "TP45") (pin "1") (pinfunction "1_1") (pintype "passive"))
      (node (ref "U10") (pin "10") (pinfunction "RST_N_10") (pintype "input"))
      (node (ref "U9") (pin "33") (pinfunction "NRSTO_33") (pintype "output"))
    )
    (net (code "42") (name "/RST8") (class "Default")
      (node (ref "TP47") (pin "1") (pinfunction "1_1") (pintype "passive"))
      (node (ref "U10") (pin "33") (pinfunction "NRSTO_33") (pintype "output"))
    )
    (net (code "43") (name "/RXD") (class "Default")
      (node (ref "TP27") (pin "1") (pinfunction "1_1") (pintype "passive"))
      (node (ref "U3") (pin "6") (pinfunction "RO_6") (pintype "output"))
    )
    (net (code "44") (name "/TXD") (class "Default")
      (node (ref "R15") (pin "2") (pinfunction "2_2") (pintype "passive"))
      (node (ref "TP26") (pin "1") (pinfunction "1_1") (pintype "passive"))
      (node (ref "U3") (pin "5") (pinfunction "CI_5") (pintype "input"))
    )
    (net (code "45") (name "/XIN") (class "Default")
      (node (ref "C29") (pin "1") (pinfunction "1_1") (pintype "passive"))
      (node (ref "R16") (pin "2") (pinfunction "2_2") (pintype "passive"))
      (node (ref "TP25") (pin "1") (pinfunction "1_1") (pintype "passive"))
      (node (ref "U3") (pin "1") (pinfunction "XIN_1") (pintype "input"))
      (node (ref "Y1") (pin "1") (pinfunction "OSC1_1") (pintype "passive"))
    )
    (net (code "46") (name "/XOUT") (class "Default")
      (node (ref "R16") (pin "1") (pinfunction "1_1") (pintype "passive"))
      (node (ref "R17") (pin "1") (pinfunction "1_1") (pintype "passive"))
      (node (ref "U3") (pin "2") (pinfunction "XOUT_2") (pintype "output"))
    )
    (net (code "47") (name "GND") (class "Default")
      (node (ref "C100") (pin "1") (pinfunction "1_1") (pintype "passive"))
      (node (ref "C101") (pin "1") (pinfunction "1_1") (pintype "passive"))
      (node (ref "C102") (pin "1") (pinfunction "1_1") (pintype "passive"))
      (node (ref "C103") (pin "1") (pinfunction "1_1") (pintype "passive"))
      (node (ref "C104") (pin "1") (pinfunction "1_1") (pintype "passive"))
      (node (ref "C105") (pin "1") (pinfunction "1_1") (pintype "passive"))
      (node (ref "C106") (pin "1") (pinfunction "1_1") (pintype "passive"))
      (node (ref "C107") (pin "1") (pinfunction "1_1") (pintype "passive"))
      (node (ref "C108") (pin "1") (pinfunction "1_1") (pintype "passive"))
      (node (ref "C109") (pin "1") (pinfunction "1_1") (pintype "passive"))
      (node (ref "C110") (pin "1") (pinfunction "1_1") (pintype "passive"))
      (node (ref "C111") (pin "1") (pinfunction "1_1") (pintype "passive"))
      (node (ref "C112") (pin "1") (pinfunction "1_1") (pintype "passive"))
      (node (ref "C113") (pin "1") (pinfunction "1_1") (pintype "passive"))
      (node (ref "C114") (pin "1") (pinfunction "1_1") (pintype "passive"))
      (node (ref "C115") (pin "1") (pinfunction "1_1") (pintype "passive"))
      (node (ref "C116") (pin "1") (pinfunction "1_1") (pintype "passive"))
      (node (ref "C117") (pin "1") (pinfunction "1_1") (pintype "passive"))
      (node (ref "C118") (pin "1") (pinfunction "1_1") (pintype "passive"))
      (node (ref "C119") (pin "1") (pinfunction "1_1") (pintype "passive"))
      (node (ref "C120") (pin "1") (pinfunction "1_1") (pintype "passive"))
      (node (ref "C121") (pin "1") (pinfunction "1_1") (pintype "passive"))
      (node (ref "C122") (pin "1") (pinfunction "1_1") (pintype "passive"))
      (node (ref "C123") (pin "1") (pinfunction "1_1") (pintype "passive"))
      (node (ref "C124") (pin "1") (pinfunction "1_1") (pintype "passive"))
      (node (ref "C125") (pin "1") (pinfunction "1_1") (pintype "passive"))
      (node (ref "C126") (pin "1") (pinfunction "1_1") (pintype "passive"))
      (node (ref "C127") (pin "1") (pinfunction "1_1") (pintype "passive"))
      (node (ref "C128") (pin "1") (pinfunction "1_1") (pintype "passive"))
      (node (ref "C129") (pin "1") (pinfunction "1_1") (pintype "passive"))
      (node (ref "C130") (pin "1") (pinfunction "1_1") (pintype "passive"))
      (node (ref "C131") (pin "1") (pinfunction "1_1") (pintype "passive"))
      (node (ref "C132") (pin "1") (pinfunction "1_1") (pintype "passive"))
      (node (ref "C133") (pin "1") (pinfunction "1_1") (pintype "passive"))
      (node (ref "C134") (pin "1") (pinfunction "1_1") (pintype "passive"))
      (node (ref "C135") (pin "1") (pinfunction "1_1") (pintype "passive"))
      (node (ref "C136") (pin "1") (pinfunction "1_1") (pintype "passive"))
      (node (ref "C137") (pin "1") (pinfunction "1_1") (pintype "passive"))
      (node (ref "C138") (pin "1") (pinfunction "1_1") (pintype "passive"))
      (node (ref "C139") (pin "1") (pinfunction "1_1") (pintype "passive"))
      (node (ref "C140") (pin "1") (pinfunction "1_1") (pintype "passive"))
      (node (ref "C141") (pin "1") (pinfunction "1_1") (pintype "passive"))
      (node (ref "C142") (pin "1") (pinfunction "1_1") (pintype "passive"))
      (node (ref "C143") (pin "1") (pinfunction "1_1") (pintype "passive"))
      (node (ref "C144") (pin "1") (pinfunction "1_1") (pintype "passive"))
      (node (ref "C145") (pin "1") (pinfunction "1_1") (pintype "passive"))
      (node (ref "C146") (pin "1") (pinfunction "1_1") (pintype "passive"))
      (node (ref "C147") (pin "1") (pinfunction "1_1") (pintype "passive"))
      (node (ref "C148") (pin "1") (pinfunction "1_1") (pintype "passive"))
      (node (ref "C149") (pin "1") (pinfunction "1_1") (pintype "passive"))
      (node (ref "C150") (pin "1") (pinfunction "1_1") (pintype "passive"))
      (node (ref "C151") (pin "1") (pinfunction "1_1") (pintype "passive"))
      (node (ref "C17") (pin "2") (pinfunction "2_2") (pintype "passive"))
      (node (ref "C18") (pin "2") (pinfunction "2_2") (pintype "passive"))
      (node (ref "C19") (pin "1") (pinfunction "1_1") (pintype "passive"))
      (node (ref "C20") (pin "1") (pinfunction "1_1") (pintype "passive"))
      (node (ref "C21") (pin "2") (pinfunction "2_2") (pintype "passive"))
      (node (ref "C22") (pin "1") (pinfunction "1_1") (pintype "passive"))
      (node (ref "C23") (pin "2") (pinfunction "2_2") (pintype "passive"))
      (node (ref "C24") (pin "1") (pinfunction "1_1") (pintype "passive"))
      (node (ref "C25") (pin "2") (pinfunction "2_2") (pintype "passive"))
      (node (ref "C26") (pin "1") (pinfunction "1_1") (pintype "passive"))
      (node (ref "C27") (pin "2") (pinfunction "2_2") (pintype "passive"))
      (node (ref "C28") (pin "1") (pinfunction "1_1") (pintype "passive"))
      (node (ref "C29") (pin "2") (pinfunction "2_2") (pintype "passive"))
      (node (ref "C30") (pin "2") (pinfunction "2_2") (pintype "passive"))
      (node (ref "C31") (pin "2") (pinfunction "2_2") (pintype "passive"))
      (node (ref "C32") (pin "1") (pinfunction "1_1") (pintype "passive"))
      (node (ref "C33") (pin "1") (pinfunction "1_1") (pintype "passive"))
      (node (ref "C34") (pin "1") (pinfunction "1_1") (pintype "passive"))
      (node (ref "C35") (pin "1") (pinfunction "1_1") (pintype "passive"))
      (node (ref "C36") (pin "1") (pinfunction "1_1") (pintype "passive"))
      (node (ref "C37") (pin "1") (pinfunction "1_1") (pintype "passive"))
      (node (ref "C38") (pin "1") (pinfunction "1_1") (pintype "passive"))
      (node (ref "C39") (pin "1") (pinfunction "1_1") (pintype "passive"))
      (node (ref "C40") (pin "1") (pinfunction "1_1") (pintype "passive"))
      (node (ref "C41") (pin "1") (pinfunction "1_1") (pintype "passive"))
      (node (ref "C42") (pin "1") (pinfunction "1_1") (pintype "passive"))
      (node (ref "C43") (pin "1") (pinfunction "1_1") (pintype "passive"))
      (node (ref "C44") (pin "1") (pinfunction "1_1") (pintype "passive"))
      (node (ref "C45") (pin "1") (pinfunction "1_1") (pintype "passive"))
      (node (ref "C46") (pin "1") (pinfunction "1_1") (pintype "passive"))
      (node (ref "C47") (pin "1") (pinfunction "1_1") (pintype "passive"))
      (node (ref "C48") (pin "1") (pinfunction "1_1") (pintype "passive"))
      (node (ref "C49") (pin "1") (pinfunction "1_1") (pintype "passive"))
      (node (ref "C50") (pin "1") (pinfunction "1_1") (pintype "passive"))
      (node (ref "C51") (pin "1") (pinfunction "1_1") (pintype "passive"))
      (node (ref "C52") (pin "1") (pinfunction "1_1") (pintype "passive"))
      (node (ref "C53") (pin "1") (pinfunction "1_1") (pintype "passive"))
      (node (ref "C54") (pin "1") (pinfunction "1_1") (pintype "passive"))
      (node (ref "C55") (pin "1") (pinfunction "1_1") (pintype "passive"))
      (node (ref "C56") (pin "1") (pinfunction "1_1") (pintype "passive"))
      (node (ref "C57") (pin "1") (pinfunction "1_1") (pintype "passive"))
      (node (ref "C58") (pin "1") (pinfunction "1_1") (pintype "passive"))
      (node (ref "C59") (pin "1") (pinfunction "1_1") (pintype "passive"))
      (node (ref "C60") (pin "1") (pinfunction "1_1") (pintype "passive"))
      (node (ref "C61") (pin "1") (pinfunction "1_1") (pintype "passive"))
      (node (ref "C62") (pin "1") (pinfunction "1_1") (pintype "passive"))
      (node (ref "C63") (pin "1") (pinfunction "1_1") (pintype "passive"))
      (node (ref "C64") (pin "1") (pinfunction "1_1") (pintype "passive"))
      (node (ref "C65") (pin "1") (pinfunction "1_1") (pintype "passive"))
      (node (ref "C66") (pin "1") (pinfunction "1_1") (pintype "passive"))
      (node (ref "C67") (pin "1") (pinfunction "1_1") (pintype "passive"))
      (node (ref "C68") (pin "1") (pinfunction "1_1") (pintype "passive"))
      (node (ref "C69") (pin "1") (pinfunction "1_1") (pintype "passive"))
      (node (ref "C70") (pin "1") (pinfunction "1_1") (pintype "passive"))
      (node (ref "C71") (pin "1") (pinfunction "1_1") (pintype "passive"))
      (node (ref "C72") (pin "1") (pinfunction "1_1") (pintype "passive"))
      (node (ref "C73") (pin "1") (pinfunction "1_1") (pintype "passive"))
      (node (ref "C74") (pin "1") (pinfunction "1_1") (pintype "passive"))
      (node (ref "C75") (pin "1") (pinfunction "1_1") (pintype "passive"))
      (node (ref "C76") (pin "1") (pinfunction "1_1") (pintype "passive"))
      (node (ref "C77") (pin "1") (pinfunction "1_1") (pintype "passive"))
      (node (ref "C78") (pin "1") (pinfunction "1_1") (pintype "passive"))
      (node (ref "C79") (pin "1") (pinfunction "1_1") (pintype "passive"))
      (node (ref "C80") (pin "1") (pinfunction "1_1") (pintype "passive"))
      (node (ref "C81") (pin "1") (pinfunction "1_1") (pintype "passive"))
      (node (ref "C82") (pin "1") (pinfunction "1_1") (pintype "passive"))
      (node (ref "C83") (pin "1") (pinfunction "1_1") (pintype "passive"))
      (node (ref "C84") (pin "1") (pinfunction "1_1") (pintype "passive"))
      (node (ref "C85") (pin "1") (pinfunction "1_1") (pintype "passive"))
      (node (ref "C86") (pin "1") (pinfunction "1_1") (pintype "passive"))
      (node (ref "C87") (pin "1") (pinfunction "1_1") (pintype "passive"))
      (node (ref "C88") (pin "2") (pinfunction "2_2") (pintype "passive"))
      (node (ref "C89") (pin "1") (pinfunction "1_1") (pintype "passive"))
      (node (ref "C90") (pin "2") (pinfunction "2_2") (pintype "passive"))
      (node (ref "C91") (pin "1") (pinfunction "1_1") (pintype "passive"))
      (node (ref "C92") (pin "2") (pinfunction "2_2") (pintype "passive"))
      (node (ref "C93") (pin "1") (pinfunction "1_1") (pintype "passive"))
      (node (ref "C94") (pin "2") (pinfunction "2_2") (pintype "passive"))
      (node (ref "C95") (pin "1") (pinfunction "1_1") (pintype "passive"))
      (node (ref "C96") (pin "1") (pinfunction "1_1") (pintype "passive"))
      (node (ref "C97") (pin "1") (pinfunction "1_1") (pintype "passive"))
      (node (ref "C98") (pin "1") (pinfunction "1_1") (pintype "passive"))
      (node (ref "C99") (pin "1") (pinfunction "1_1") (pintype "passive"))
      (node (ref "M4") (pin "0") (pinfunction "PIN_0") (pintype "power_in"))
      (node (ref "M5") (pin "0") (pinfunction "PIN_0") (pintype "power_in"))
      (node (ref "M6") (pin "0") (pinfunction "PIN_0") (pintype "power_in"))
      (node (ref "M7") (pin "0") (pinfunction "PIN_0") (pintype "power_in"))
      (node (ref "M8") (pin "0") (pinfunction "PIN_0") (pintype "power_in"))
      (node (ref "U10") (pin "12") (pinfunction "GND_12") (pintype "power_in"))
      (node (ref "U10") (pin "13") (pinfunction "VSS_13") (pintype "power_in"))
      (node (ref "U10") (pin "15") (pinfunction "ADDR0_15") (pintype "passive"))
      (node (ref "U10") (pin "16") (pinfunction "ADDR1_16") (pintype "passive"))
      (node (ref "U10") (pin "18") (pinfunction "GND_18") (pintype "power_in"))
      (node (ref "U10") (pin "19") (pinfunction "ADDR2_19") (pintype "passive"))
      (node (ref "U10") (pin "22") (pinfunction "GND_22") (pintype "power_in"))
      (node (ref "U10") (pin "26") (pinfunction "GND_26") (pintype "power_in"))
      (node (ref "U10") (pin "27") (pinfunction "ADDR6_27") (pintype "passive"))
      (node (ref "U10") (pin "28") (pinfunction "ADDR7_28") (pintype "passive"))
      (node (ref "U10") (pin "3") (pinfunction "GND_3") (pintype "power_in"))
      (node (ref "U10") (pin "30") (pinfunction "VSS_30") (pintype "power_in"))
      (node (ref "U10") (pin "31") (pinfunction "GND_31") (pintype "power_in"))
      (node (ref "U10") (pin "35") (pinfunction "GND_35") (pintype "power_in"))
      (node (ref "U10") (pin "41") (pinfunction "GND_41") (pintype "power_in"))
      (node (ref "U10") (pin "42") (pinfunction "VSS_42") (pintype "power_in"))
      (node (ref "U10") (pin "45") (pinfunction "SMODE_45") (pintype "passive"))
      (node (ref "U10") (pin "46") (pinfunction "GND_46") (pintype "power_in"))
      (node (ref "U10") (pin "50") (pinfunction "TEST_50") (pintype "passive"))
      (node (ref "U10") (pin "52") (pinfunction "GND_52") (pintype "power_in"))
      (node (ref "U10") (pin "53") (pinfunction "PLL_DVSS_53") (pintype "power_in"))
      (node (ref "U10") (pin "56") (pinfunction "PLL_AVSS_56") (pintype "power_in"))
      (node (ref "U10") (pin "57") (pinfunction "GND_57") (pintype "power_in"))
      (node (ref "U10") (pin "8") (pinfunction "GND_8") (pintype "power_in"))
      (node (ref "U3") (pin "12") (pinfunction "GND_12") (pintype "power_in"))
      (node (ref "U3") (pin "13") (pinfunction "VSS_13") (pintype "power_in"))
      (node (ref "U3") (pin "15") (pinfunction "ADDR0_15") (pintype "passive"))
      (node (ref "U3") (pin "16") (pinfunction "ADDR1_16") (pintype "passive"))
      (node (ref "U3") (pin "18") (pinfunction "GND_18") (pintype "power_in"))
      (node (ref "U3") (pin "19") (pinfunction "ADDR2_19") (pintype "passive"))
      (node (ref "U3") (pin "20") (pinfunction "ADDR3_20") (pintype "passive"))
      (node (ref "U3") (pin "22") (pinfunction "GND_22") (pintype "power_in"))
      (node (ref "U3") (pin "23") (pinfunction "ADDR4_23") (pintype "passive"))
      (node (ref "U3") (pin "24") (pinfunction "ADDR5_24") (pintype "passive"))
      (node (ref "U3") (pin "26") (pinfunction "GND_26") (pintype "power_in"))
      (node (ref "U3") (pin "27") (pinfunction "ADDR6_27") (pintype "passive"))
      (node (ref "U3") (pin "28") (pinfunction "ADDR7_28") (pintype "passive"))
      (node (ref "U3") (pin "3") (pinfunction "GND_3") (pintype "power_in"))
      (node (ref "U3") (pin "30") (pinfunction "VSS_30") (pintype "power_in"))
      (node (ref "U3") (pin "31") (pinfunction "GND_31") (pintype "power_in"))
      (node (ref "U3") (pin "35") (pinfunction "GND_35") (pintype "power_in"))
      (node (ref "U3") (pin "41") (pinfunction "GND_41") (pintype "power_in"))
      (node (ref "U3") (pin "42") (pinfunction "VSS_42") (pintype "power_in"))
      (node (ref "U3") (pin "45") (pinfunction "SMODE_45") (pintype "passive"))
      (node (ref "U3") (pin "46") (pinfunction "GND_46") (pintype "power_in"))
      (node (ref "U3") (pin "50") (pinfunction "TEST_50") (pintype "passive"))
      (node (ref "U3") (pin "52") (pinfunction "GND_52") (pintype "power_in"))
      (node (ref "U3") (pin "53") (pinfunction "PLL_DVSS_53") (pintype "power_in"))
      (node (ref "U3") (pin "56") (pinfunction "PLL_AVSS_56") (pintype "power_in"))
      (node (ref "U3") (pin "57") (pinfunction "GND_57") (pintype "power_in"))
      (node (ref "U3") (pin "8") (pinfunction "GND_8") (pintype "power_in"))
      (node (ref "U3") (pin "9") (pinfunction "BI_9") (pintype "input"))
      (node (ref "U4") (pin "12") (pinfunction "GND_12") (pintype "power_in"))
      (node (ref "U4") (pin "13") (pinfunction "VSS_13") (pintype "power_in"))
      (node (ref "U4") (pin "15") (pinfunction "ADDR0_15") (pintype "passive"))
      (node (ref "U4") (pin "16") (pinfunction "ADDR1_16") (pintype "passive"))
      (node (ref "U4") (pin "18") (pinfunction "GND_18") (pintype "power_in"))
      (node (ref "U4") (pin "19") (pinfunction "ADDR2_19") (pintype "passive"))
      (node (ref "U4") (pin "22") (pinfunction "GND_22") (pintype "power_in"))
      (node (ref "U4") (pin "23") (pinfunction "ADDR4_23") (pintype "passive"))
      (node (ref "U4") (pin "24") (pinfunction "ADDR5_24") (pintype "passive"))
      (node (ref "U4") (pin "26") (pinfunction "GND_26") (pintype "power_in"))
      (node (ref "U4") (pin "27") (pinfunction "ADDR6_27") (pintype "passive"))
      (node (ref "U4") (pin "28") (pinfunction "ADDR7_28") (pintype "passive"))
      (node (ref "U4") (pin "3") (pinfunction "GND_3") (pintype "power_in"))
      (node (ref "U4") (pin "30") (pinfunction "VSS_30") (pintype "power_in"))
      (node (ref "U4") (pin "31") (pinfunction "GND_31") (pintype "power_in"))
      (node (ref "U4") (pin "35") (pinfunction "GND_35") (pintype "power_in"))
      (node (ref "U4") (pin "41") (pinfunction "GND_41") (pintype "power_in"))
      (node (ref "U4") (pin "42") (pinfunction "VSS_42") (pintype "power_in"))
      (node (ref "U4") (pin "45") (pinfunction "SMODE_45") (pintype "passive"))
      (node (ref "U4") (pin "46") (pinfunction "GND_46") (pintype "power_in"))
      (node (ref "U4") (pin "50") (pinfunction "TEST_50") (pintype "passive"))
      (node (ref "U4") (pin "52") (pinfunction "GND_52") (pintype "power_in"))
      (node (ref "U4") (pin "53") (pinfunction "PLL_DVSS_53") (pintype "power_in"))
      (node (ref "U4") (pin "56") (pinfunction "PLL_AVSS_56") (pintype "power_in"))
      (node (ref "U4") (pin "57") (pinfunction "GND_57") (pintype "power_in"))
      (node (ref "U4") (pin "8") (pinfunction "GND_8") (pintype "power_in"))
      (node (ref "U5") (pin "12") (pinfunction "GND_12") (pintype "power_in"))
      (node (ref "U5") (pin "13") (pinfunction "VSS_13") (pintype "power_in"))
      (node (ref "U5") (pin "15") (pinfunction "ADDR0_15") (pintype "passive"))
      (node (ref "U5") (pin "16") (pinfunction "ADDR1_16") (pintype "passive"))
      (node (ref "U5") (pin "18") (pinfunction "GND_18") (pintype "power_in"))
      (node (ref "U5") (pin "19") (pinfunction "ADDR2_19") (pintype "passive"))
      (node (ref "U5") (pin "20") (pinfunction "ADDR3_20") (pintype "passive"))
      (node (ref "U5") (pin "22") (pinfunction "GND_22") (pintype "power_in"))
      (node (ref "U5") (pin "24") (pinfunction "ADDR5_24") (pintype "passive"))
      (node (ref "U5") (pin "26") (pinfunction "GND_26") (pintype "power_in"))
      (node (ref "U5") (pin "27") (pinfunction "ADDR6_27") (pintype "passive"))
      (node (ref "U5") (pin "28") (pinfunction "ADDR7_28") (pintype "passive"))
      (node (ref "U5") (pin "3") (pinfunction "GND_3") (pintype "power_in"))
      (node (ref "U5") (pin "30") (pinfunction "VSS_30") (pintype "power_in"))
      (node (ref "U5") (pin "31") (pinfunction "GND_31") (pintype "power_in"))
      (node (ref "U5") (pin "35") (pinfunction "GND_35") (pintype "power_in"))
      (node (ref "U5") (pin "41") (pinfunction "GND_41") (pintype "power_in"))
      (node (ref "U5") (pin "42") (pinfunction "VSS_42") (pintype "power_in"))
      (node (ref "U5") (pin "45") (pinfunction "SMODE_45") (pintype "passive"))
      (node (ref "U5") (pin "46") (pinfunction "GND_46") (pintype "power_in"))
      (node (ref "U5") (pin "50") (pinfunction "TEST_50") (pintype "passive"))
      (node (ref "U5") (pin "52") (pinfunction "GND_52") (pintype "power_in"))
      (node (ref "U5") (pin "53") (pinfunction "PLL_DVSS_53") (pintype "power_in"))
      (node (ref "U5") (pin "56") (pinfunction "PLL_AVSS_56") (pintype "power_in"))
      (node (ref "U5") (pin "57") (pinfunction "GND_57") (pintype "power_in"))
      (node (ref "U5") (pin "8") (pinfunction "GND_8") (pintype "power_in"))
      (node (ref "U6") (pin "12") (pinfunction "GND_12") (pintype "power_in"))
      (node (ref "U6") (pin "13") (pinfunction "VSS_13") (pintype "power_in"))
      (node (ref "U6") (pin "15") (pinfunction "ADDR0_15") (pintype "passive"))
      (node (ref "U6") (pin "16") (pinfunction "ADDR1_16") (pintype "passive"))
      (node (ref "U6") (pin "18") (pinfunction "GND_18") (pintype "power_in"))
      (node (ref "U6") (pin "19") (pinfunction "ADDR2_19") (pintype "passive"))
      (node (ref "U6") (pin "22") (pinfunction "GND_22") (pintype "power_in"))
      (node (ref "U6") (pin "24") (pinfunction "ADDR5_24") (pintype "passive"))
      (node (ref "U6") (pin "26") (pinfunction "GND_26") (pintype "power_in"))
      (node (ref "U6") (pin "27") (pinfunction "ADDR6_27") (pintype "passive"))
      (node (ref "U6") (pin "28") (pinfunction "ADDR7_28") (pintype "passive"))
      (node (ref "U6") (pin "3") (pinfunction "GND_3") (pintype "power_in"))
      (node (ref "U6") (pin "30") (pinfunction "VSS_30") (pintype "power_in"))
      (node (ref "U6") (pin "31") (pinfunction "GND_31") (pintype "power_in"))
      (node (ref "U6") (pin "35") (pinfunction "GND_35") (pintype "power_in"))
      (node (ref "U6") (pin "41") (pinfunction "GND_41") (pintype "power_in"))
      (node (ref "U6") (pin "42") (pinfunction "VSS_42") (pintype "power_in"))
      (node (ref "U6") (pin "45") (pinfunction "SMODE_45") (pintype "passive"))
      (node (ref "U6") (pin "46") (pinfunction "GND_46") (pintype "power_in"))
      (node (ref "U6") (pin "50") (pinfunction "TEST_50") (pintype "passive"))
      (node (ref "U6") (pin "52") (pinfunction "GND_52") (pintype "power_in"))
      (node (ref "U6") (pin "53") (pinfunction "PLL_DVSS_53") (pintype "power_in"))
      (node (ref "U6") (pin "56") (pinfunction "PLL_AVSS_56") (pintype "power_in"))
      (node (ref "U6") (pin "57") (pinfunction "GND_57") (pintype "power_in"))
      (node (ref "U6") (pin "8") (pinfunction "GND_8") (pintype "power_in"))
      (node (ref "U7") (pin "12") (pinfunction "GND_12") (pintype "power_in"))
      (node (ref "U7") (pin "13") (pinfunction "VSS_13") (pintype "power_in"))
      (node (ref "U7") (pin "15") (pinfunction "ADDR0_15") (pintype "passive"))
      (node (ref "U7") (pin "16") (pinfunction "ADDR1_16") (pintype "passive"))
      (node (ref "U7") (pin "18") (pinfunction "GND_18") (pintype "power_in"))
      (node (ref "U7") (pin "19") (pinfunction "ADDR2_19") (pintype "passive"))
      (node (ref "U7") (pin "20") (pinfunction "ADDR3_20") (pintype "passive"))
      (node (ref "U7") (pin "22") (pinfunction "GND_22") (pintype "power_in"))
      (node (ref "U7") (pin "23") (pinfunction "ADDR4_23") (pintype "passive"))
      (node (ref "U7") (pin "26") (pinfunction "GND_26") (pintype "power_in"))
      (node (ref "U7") (pin "27") (pinfunction "ADDR6_27") (pintype "passive"))
      (node (ref "U7") (pin "28") (pinfunction "ADDR7_28") (pintype "passive"))
      (node (ref "U7") (pin "3") (pinfunction "GND_3") (pintype "power_in"))
      (node (ref "U7") (pin "30") (pinfunction "VSS_30") (pintype "power_in"))
      (node (ref "U7") (pin "31") (pinfunction "GND_31") (pintype "power_in"))
      (node (ref "U7") (pin "35") (pinfunction "GND_35") (pintype "power_in"))
      (node (ref "U7") (pin "41") (pinfunction "GND_41") (pintype "power_in"))
      (node (ref "U7") (pin "42") (pinfunction "VSS_42") (pintype "power_in"))
      (node (ref "U7") (pin "45") (pinfunction "SMODE_45") (pintype "passive"))
      (node (ref "U7") (pin "46") (pinfunction "GND_46") (pintype "power_in"))
      (node (ref "U7") (pin "50") (pinfunction "TEST_50") (pintype "passive"))
      (node (ref "U7") (pin "52") (pinfunction "GND_52") (pintype "power_in"))
      (node (ref "U7") (pin "53") (pinfunction "PLL_DVSS_53") (pintype "power_in"))
      (node (ref "U7") (pin "56") (pinfunction "PLL_AVSS_56") (pintype "power_in"))
      (node (ref "U7") (pin "57") (pinfunction "GND_57") (pintype "power_in"))
      (node (ref "U7") (pin "8") (pinfunction "GND_8") (pintype "power_in"))
      (node (ref "U8") (pin "12") (pinfunction "GND_12") (pintype "power_in"))
      (node (ref "U8") (pin "13") (pinfunction "VSS_13") (pintype "power_in"))
      (node (ref "U8") (pin "15") (pinfunction "ADDR0_15") (pintype "passive"))
      (node (ref "U8") (pin "16") (pinfunction "ADDR1_16") (pintype "passive"))
      (node (ref "U8") (pin "18") (pinfunction "GND_18") (pintype "power_in"))
      (node (ref "U8") (pin "19") (pinfunction "ADDR2_19") (pintype "passive"))
      (node (ref "U8") (pin "22") (pinfunction "GND_22") (pintype "power_in"))
      (node (ref "U8") (pin "23") (pinfunction "ADDR4_23") (pintype "passive"))
      (node (ref "U8") (pin "26") (pinfunction "GND_26") (pintype "power_in"))
      (node (ref "U8") (pin "27") (pinfunction "ADDR6_27") (pintype "passive"))
      (node (ref "U8") (pin "28") (pinfunction "ADDR7_28") (pintype "passive"))
      (node (ref "U8") (pin "3") (pinfunction "GND_3") (pintype "power_in"))
      (node (ref "U8") (pin "30") (pinfunction "VSS_30") (pintype "power_in"))
      (node (ref "U8") (pin "31") (pinfunction "GND_31") (pintype "power_in"))
      (node (ref "U8") (pin "35") (pinfunction "GND_35") (pintype "power_in"))
      (node (ref "U8") (pin "41") (pinfunction "GND_41") (pintype "power_in"))
      (node (ref "U8") (pin "42") (pinfunction "VSS_42") (pintype "power_in"))
      (node (ref "U8") (pin "45") (pinfunction "SMODE_45") (pintype "passive"))
      (node (ref "U8") (pin "46") (pinfunction "GND_46") (pintype "power_in"))
      (node (ref "U8") (pin "50") (pinfunction "TEST_50") (pintype "passive"))
      (node (ref "U8") (pin "52") (pinfunction "GND_52") (pintype "power_in"))
      (node (ref "U8") (pin "53") (pinfunction "PLL_DVSS_53") (pintype "power_in"))
      (node (ref "U8") (pin "56") (pinfunction "PLL_AVSS_56") (pintype "power_in"))
      (node (ref "U8") (pin "57") (pinfunction "GND_57") (pintype "power_in"))
      (node (ref "U8") (pin "8") (pinfunction "GND_8") (pintype "power_in"))
      (node (ref "U9") (pin "12") (pinfunction "GND_12") (pintype "power_in"))
      (node (ref "U9") (pin "13") (pinfunction "VSS_13") (pintype "power_in"))
      (node (ref "U9") (pin "15") (pinfunction "ADDR0_15") (pintype "passive"))
      (node (ref "U9") (pin "16") (pinfunction "ADDR1_16") (pintype "passive"))
      (node (ref "U9") (pin "18") (pinfunction "GND_18") (pintype "power_in"))
      (node (ref "U9") (pin "19") (pinfunction "ADDR2_19") (pintype "passive"))
      (node (ref "U9") (pin "20") (pinfunction "ADDR3_20") (pintype "passive"))
      (node (ref "U9") (pin "22") (pinfunction "GND_22") (pintype "power_in"))
      (node (ref "U9") (pin "26") (pinfunction "GND_26") (pintype "power_in"))
      (node (ref "U9") (pin "27") (pinfunction "ADDR6_27") (pintype "passive"))
      (node (ref "U9") (pin "28") (pinfunction "ADDR7_28") (pintype "passive"))
      (node (ref "U9") (pin "3") (pinfunction "GND_3") (pintype "power_in"))
      (node (ref "U9") (pin "30") (pinfunction "VSS_30") (pintype "power_in"))
      (node (ref "U9") (pin "31") (pinfunction "GND_31") (pintype "power_in"))
      (node (ref "U9") (pin "35") (pinfunction "GND_35") (pintype "power_in"))
      (node (ref "U9") (pin "41") (pinfunction "GND_41") (pintype "power_in"))
      (node (ref "U9") (pin "42") (pinfunction "VSS_42") (pintype "power_in"))
      (node (ref "U9") (pin "45") (pinfunction "SMODE_45") (pintype "passive"))
      (node (ref "U9") (pin "46") (pinfunction "GND_46") (pintype "power_in"))
      (node (ref "U9") (pin "50") (pinfunction "TEST_50") (pintype "passive"))
      (node (ref "U9") (pin "52") (pinfunction "GND_52") (pintype "power_in"))
      (node (ref "U9") (pin "53") (pinfunction "PLL_DVSS_53") (pintype "power_in"))
      (node (ref "U9") (pin "56") (pinfunction "PLL_AVSS_56") (pintype "power_in"))
      (node (ref "U9") (pin "57") (pinfunction "GND_57") (pintype "power_in"))
      (node (ref "U9") (pin "8") (pinfunction "GND_8") (pintype "power_in"))
    )
    (net (code "48") (name "Net-(U3-PLL_AVDD)") (class "Default")
      (node (ref "C22") (pin "2") (pinfunction "2_2") (pintype "passive"))
      (node (ref "FB1") (pin "1") (pinfunction "1_1") (pintype "passive"))
      (node (ref "U3") (pin "55") (pinfunction "PLL_AVDD_55") (pintype "power_in"))
    )
    (net (code "49") (name "Net-(U4-PLL_AVDD)") (class "Default")
      (node (ref "C24") (pin "2") (pinfunction "2_2") (pintype "passive"))
      (node (ref "FB2") (pin "1") (pinfunction "1_1") (pintype "passive"))
      (node (ref "U4") (pin "55") (pinfunction "PLL_AVDD_55") (pintype "power_in"))
    )
    (net (code "50") (name "Net-(U5-PLL_AVDD)") (class "Default")
      (node (ref "C26") (pin "2") (pinfunction "2_2") (pintype "passive"))
      (node (ref "FB3") (pin "1") (pinfunction "1_1") (pintype "passive"))
      (node (ref "U5") (pin "55") (pinfunction "PLL_AVDD_55") (pintype "power_in"))
    )
    (net (code "51") (name "Net-(U6-PLL_AVDD)") (class "Default")
      (node (ref "C28") (pin "2") (pinfunction "2_2") (pintype "passive"))
      (node (ref "FB4") (pin "1") (pinfunction "1_1") (pintype "passive"))
      (node (ref "U6") (pin "55") (pinfunction "PLL_AVDD_55") (pintype "power_in"))
    )
    (net (code "52") (name "Net-(U7-PLL_AVDD)") (class "Default")
      (node (ref "C89") (pin "2") (pinfunction "2_2") (pintype "passive"))
      (node (ref "FB5") (pin "1") (pinfunction "1_1") (pintype "passive"))
      (node (ref "U7") (pin "55") (pinfunction "PLL_AVDD_55") (pintype "power_in"))
    )
    (net (code "53") (name "Net-(U8-PLL_AVDD)") (class "Default")
      (node (ref "C91") (pin "2") (pinfunction "2_2") (pintype "passive"))
      (node (ref "FB6") (pin "1") (pinfunction "1_1") (pintype "passive"))
      (node (ref "U8") (pin "55") (pinfunction "PLL_AVDD_55") (pintype "power_in"))
    )
    (net (code "54") (name "Net-(U9-PLL_AVDD)") (class "Default")
      (node (ref "C93") (pin "2") (pinfunction "2_2") (pintype "passive"))
      (node (ref "FB7") (pin "1") (pinfunction "1_1") (pintype "passive"))
      (node (ref "U9") (pin "55") (pinfunction "PLL_AVDD_55") (pintype "power_in"))
    )
    (net (code "55") (name "Net-(U10-PLL_AVDD)") (class "Default")
      (node (ref "C95") (pin "2") (pinfunction "2_2") (pintype "passive"))
      (node (ref "FB8") (pin "1") (pinfunction "1_1") (pintype "passive"))
      (node (ref "U10") (pin "55") (pinfunction "PLL_AVDD_55") (pintype "power_in"))
    )
    (net (code "56") (name "Net-(Y1-OSC2)") (class "Default")
      (node (ref "C30") (pin "1") (pinfunction "1_1") (pintype "passive"))
      (node (ref "R17") (pin "2") (pinfunction "2_2") (pintype "passive"))
      (node (ref "Y1") (pin "3") (pinfunction "OSC2_3") (pintype "passive"))
    )
    (net (code "57") (name "VDD1") (class "Default")
      (node (ref "C108") (pin "2") (pinfunction "2_2") (pintype "passive"))
      (node (ref "C109") (pin "2") (pinfunction "2_2") (pintype "passive"))
      (node (ref "C110") (pin "2") (pinfunction "2_2") (pintype "passive"))
      (node (ref "C111") (pin "2") (pinfunction "2_2") (pintype "passive"))
      (node (ref "C112") (pin "2") (pinfunction "2_2") (pintype "passive"))
      (node (ref "C113") (pin "2") (pinfunction "2_2") (pintype "passive"))
      (node (ref "C114") (pin "2") (pinfunction "2_2") (pintype "passive"))
      (node (ref "C115") (pin "2") (pinfunction "2_2") (pintype "passive"))
      (node (ref "C116") (pin "2") (pinfunction "2_2") (pintype "passive"))
      (node (ref "C117") (pin "2") (pinfunction "2_2") (pintype "passive"))
      (node (ref "C118") (pin "2") (pinfunction "2_2") (pintype "passive"))
      (node (ref "C119") (pin "2") (pinfunction "2_2") (pintype "passive"))
      (node (ref "C120") (pin "2") (pinfunction "2_2") (pintype "passive"))
      (node (ref "C121") (pin "2") (pinfunction "2_2") (pintype "passive"))
      (node (ref "C122") (pin "2") (pinfunction "2_2") (pintype "passive"))
      (node (ref "C123") (pin "2") (pinfunction "2_2") (pintype "passive"))
      (node (ref "C124") (pin "2") (pinfunction "2_2") (pintype "passive"))
      (node (ref "C125") (pin "2") (pinfunction "2_2") (pintype "passive"))
      (node (ref "C126") (pin "2") (pinfunction "2_2") (pintype "passive"))
      (node (ref "C127") (pin "2") (pinfunction "2_2") (pintype "passive"))
      (node (ref "C128") (pin "2") (pinfunction "2_2") (pintype "passive"))
      (node (ref "C129") (pin "2") (pinfunction "2_2") (pintype "passive"))
      (node (ref "C130") (pin "2") (pinfunction "2_2") (pintype "passive"))
      (node (ref "C131") (pin "2") (pinfunction "2_2") (pintype "passive"))
      (node (ref "C132") (pin "2") (pinfunction "2_2") (pintype "passive"))
      (node (ref "C133") (pin "2") (pinfunction "2_2") (pintype "passive"))
      (node (ref "C134") (pin "2") (pinfunction "2_2") (pintype "passive"))
      (node (ref "C135") (pin "2") (pinfunction "2_2") (pintype "passive"))
      (node (ref "C136") (pin "2") (pinfunction "2_2") (pintype "passive"))
      (node (ref "C137") (pin "2") (pinfunction "2_2") (pintype "passive"))
      (node (ref "C138") (pin "2") (pinfunction "2_2") (pintype "passive"))
      (node (ref "C139") (pin "2") (pinfunction "2_2") (pintype "passive"))
      (node (ref "C140") (pin "2") (pinfunction "2_2") (pintype "passive"))
      (node (ref "C141") (pin "2") (pinfunction "2_2") (pintype "passive"))
      (node (ref "C142") (pin "2") (pinfunction "2_2") (pintype "passive"))
      (node (ref "C143") (pin "2") (pinfunction "2_2") (pintype "passive"))
      (node (ref "C144") (pin "2") (pinfunction "2_2") (pintype "passive"))
      (node (ref "C145") (pin "2") (pinfunction "2_2") (pintype "passive"))
      (node (ref "C146") (pin "2") (pinfunction "2_2") (pintype "passive"))
      (node (ref "C147") (pin "2") (pinfunction "2_2") (pintype "passive"))
      (node (ref "C148") (pin "2") (pinfunction "2_2") (pintype "passive"))
      (node (ref "C149") (pin "2") (pinfunction "2_2") (pintype "passive"))
      (node (ref "C150") (pin "2") (pinfunction "2_2") (pintype "passive"))
      (node (ref "C151") (pin "2") (pinfunction "2_2") (pintype "passive"))
      (node (ref "C17") (pin "1") (pinfunction "1_1") (pintype "passive"))
      (node (ref "C18") (pin "1") (pinfunction "1_1") (pintype "passive"))
      (node (ref "C19") (pin "2") (pinfunction "2_2") (pintype "passive"))
      (node (ref "C20") (pin "2") (pinfunction "2_2") (pintype "passive"))
      (node (ref "C44") (pin "2") (pinfunction "2_2") (pintype "passive"))
      (node (ref "C45") (pin "2") (pinfunction "2_2") (pintype "passive"))
      (node (ref "C46") (pin "2") (pinfunction "2_2") (pintype "passive"))
      (node (ref "C47") (pin "2") (pinfunction "2_2") (pintype "passive"))
      (node (ref "C48") (pin "2") (pinfunction "2_2") (pintype "passive"))
      (node (ref "C49") (pin "2") (pinfunction "2_2") (pintype "passive"))
      (node (ref "C50") (pin "2") (pinfunction "2_2") (pintype "passive"))
      (node (ref "C51") (pin "2") (pinfunction "2_2") (pintype "passive"))
      (node (ref "C52") (pin "2") (pinfunction "2_2") (pintype "passive"))
      (node (ref "C53") (pin "2") (pinfunction "2_2") (pintype "passive"))
      (node (ref "C54") (pin "2") (pinfunction "2_2") (pintype "passive"))
      (node (ref "C55") (pin "2") (pinfunction "2_2") (pintype "passive"))
      (node (ref "C56") (pin "2") (pinfunction "2_2") (pintype "passive"))
      (node (ref "C57") (pin "2") (pinfunction "2_2") (pintype "passive"))
      (node (ref "C58") (pin "2") (pinfunction "2_2") (pintype "passive"))
      (node (ref "C59") (pin "2") (pinfunction "2_2") (pintype "passive"))
      (node (ref "C60") (pin "2") (pinfunction "2_2") (pintype "passive"))
      (node (ref "C61") (pin "2") (pinfunction "2_2") (pintype "passive"))
      (node (ref "C62") (pin "2") (pinfunction "2_2") (pintype "passive"))
      (node (ref "C63") (pin "2") (pinfunction "2_2") (pintype "passive"))
      (node (ref "C64") (pin "2") (pinfunction "2_2") (pintype "passive"))
      (node (ref "C65") (pin "2") (pinfunction "2_2") (pintype "passive"))
      (node (ref "C66") (pin "2") (pinfunction "2_2") (pintype "passive"))
      (node (ref "C67") (pin "2") (pinfunction "2_2") (pintype "passive"))
      (node (ref "C68") (pin "2") (pinfunction "2_2") (pintype "passive"))
      (node (ref "C69") (pin "2") (pinfunction "2_2") (pintype "passive"))
      (node (ref "C70") (pin "2") (pinfunction "2_2") (pintype "passive"))
      (node (ref "C71") (pin "2") (pinfunction "2_2") (pintype "passive"))
      (node (ref "C72") (pin "2") (pinfunction "2_2") (pintype "passive"))
      (node (ref "C73") (pin "2") (pinfunction "2_2") (pintype "passive"))
      (node (ref "C74") (pin "2") (pinfunction "2_2") (pintype "passive"))
      (node (ref "C75") (pin "2") (pinfunction "2_2") (pintype "passive"))
      (node (ref "C76") (pin "2") (pinfunction "2_2") (pintype "passive"))
      (node (ref "C77") (pin "2") (pinfunction "2_2") (pintype "passive"))
      (node (ref "C78") (pin "2") (pinfunction "2_2") (pintype "passive"))
      (node (ref "C79") (pin "2") (pinfunction "2_2") (pintype "passive"))
      (node (ref "C80") (pin "2") (pinfunction "2_2") (pintype "passive"))
      (node (ref "C81") (pin "2") (pinfunction "2_2") (pintype "passive"))
      (node (ref "C82") (pin "2") (pinfunction "2_2") (pintype "passive"))
      (node (ref "C83") (pin "2") (pinfunction "2_2") (pintype "passive"))
      (node (ref "C84") (pin "2") (pinfunction "2_2") (pintype "passive"))
      (node (ref "C85") (pin "2") (pinfunction "2_2") (pintype "passive"))
      (node (ref "C86") (pin "2") (pinfunction "2_2") (pintype "passive"))
      (node (ref "C87") (pin "2") (pinfunction "2_2") (pintype "passive"))
      (node (ref "U10") (pin "11") (pinfunction "VDD_11") (pintype "power_in"))
      (node (ref "U10") (pin "17") (pinfunction "VDD_17") (pintype "power_in"))
      (node (ref "U10") (pin "21") (pinfunction "VDD_21") (pintype "power_in"))
      (node (ref "U10") (pin "25") (pinfunction "VDD_25") (pintype "power_in"))
      (node (ref "U10") (pin "32") (pinfunction "VDD_32") (pintype "power_in"))
      (node (ref "U10") (pin "36") (pinfunction "VDD_36") (pintype "power_in"))
      (node (ref "U10") (pin "4") (pinfunction "VDD_4") (pintype "power_in"))
      (node (ref "U10") (pin "40") (pinfunction "VDD_40") (pintype "power_in"))
      (node (ref "U10") (pin "47") (pinfunction "VDD_47") (pintype "power_in"))
      (node (ref "U10") (pin "51") (pinfunction "VDD_51") (pintype "power_in"))
      (node (ref "U10") (pin "7") (pinfunction "VDD_7") (pintype "power_in"))
      (node (ref "U3") (pin "11") (pinfunction "VDD_11") (pintype "power_in"))
      (node (ref "U3") (pin "17") (pinfunction "VDD_17") (pintype "power_in"))
      (node (ref "U3") (pin "21") (pinfunction "VDD_21") (pintype "power_in"))
      (node (ref "U3") (pin "25") (pinfunction "VDD_25") (pintype "power_in"))
      (node (ref "U3") (pin "32") (pinfunction "VDD_32") (pintype "power_in"))
      (node (ref "U3") (pin "36") (pinfunction "VDD_36") (pintype "power_in"))
      (node (ref "U3") (pin "4") (pinfunction "VDD_4") (pintype "power_in"))
      (node (ref "U3") (pin "40") (pinfunction "VDD_40") (pintype "power_in"))
      (node (ref "U3") (pin "47") (pinfunction "VDD_47") (pintype "power_in"))
      (node (ref "U3") (pin "51") (pinfunction "VDD_51") (pintype "power_in"))
      (node (ref "U3") (pin "7") (pinfunction "VDD_7") (pintype "power_in"))
      (node (ref "U4") (pin "11") (pinfunction "VDD_11") (pintype "power_in"))
      (node (ref "U4") (pin "17") (pinfunction "VDD_17") (pintype "power_in"))
      (node (ref "U4") (pin "21") (pinfunction "VDD_21") (pintype "power_in"))
      (node (ref "U4") (pin "25") (pinfunction "VDD_25") (pintype "power_in"))
      (node (ref "U4") (pin "32") (pinfunction "VDD_32") (pintype "power_in"))
      (node (ref "U4") (pin "36") (pinfunction "VDD_36") (pintype "power_in"))
      (node (ref "U4") (pin "4") (pinfunction "VDD_4") (pintype "power_in"))
      (node (ref "U4") (pin "40") (pinfunction "VDD_40") (pintype "power_in"))
      (node (ref "U4") (pin "47") (pinfunction "VDD_47") (pintype "power_in"))
      (node (ref "U4") (pin "51") (pinfunction "VDD_51") (pintype "power_in"))
      (node (ref "U4") (pin "7") (pinfunction "VDD_7") (pintype "power_in"))
      (node (ref "U5") (pin "11") (pinfunction "VDD_11") (pintype "power_in"))
      (node (ref "U5") (pin "17") (pinfunction "VDD_17") (pintype "power_in"))
      (node (ref "U5") (pin "21") (pinfunction "VDD_21") (pintype "power_in"))
      (node (ref "U5") (pin "25") (pinfunction "VDD_25") (pintype "power_in"))
      (node (ref "U5") (pin "32") (pinfunction "VDD_32") (pintype "power_in"))
      (node (ref "U5") (pin "36") (pinfunction "VDD_36") (pintype "power_in"))
      (node (ref "U5") (pin "4") (pinfunction "VDD_4") (pintype "power_in"))
      (node (ref "U5") (pin "40") (pinfunction "VDD_40") (pintype "power_in"))
      (node (ref "U5") (pin "47") (pinfunction "VDD_47") (pintype "power_in"))
      (node (ref "U5") (pin "51") (pinfunction "VDD_51") (pintype "power_in"))
      (node (ref "U5") (pin "7") (pinfunction "VDD_7") (pintype "power_in"))
      (node (ref "U6") (pin "11") (pinfunction "VDD_11") (pintype "power_in"))
      (node (ref "U6") (pin "17") (pinfunction "VDD_17") (pintype "power_in"))
      (node (ref "U6") (pin "21") (pinfunction "VDD_21") (pintype "power_in"))
      (node (ref "U6") (pin "25") (pinfunction "VDD_25") (pintype "power_in"))
      (node (ref "U6") (pin "32") (pinfunction "VDD_32") (pintype "power_in"))
      (node (ref "U6") (pin "36") (pinfunction "VDD_36") (pintype "power_in"))
      (node (ref "U6") (pin "4") (pinfunction "VDD_4") (pintype "power_in"))
      (node (ref "U6") (pin "40") (pinfunction "VDD_40") (pintype "power_in"))
      (node (ref "U6") (pin "47") (pinfunction "VDD_47") (pintype "power_in"))
      (node (ref "U6") (pin "51") (pinfunction "VDD_51") (pintype "power_in"))
      (node (ref "U6") (pin "7") (pinfunction "VDD_7") (pintype "power_in"))
      (node (ref "U7") (pin "11") (pinfunction "VDD_11") (pintype "power_in"))
      (node (ref "U7") (pin "17") (pinfunction "VDD_17") (pintype "power_in"))
      (node (ref "U7") (pin "21") (pinfunction "VDD_21") (pintype "power_in"))
      (node (ref "U7") (pin "25") (pinfunction "VDD_25") (pintype "power_in"))
      (node (ref "U7") (pin "32") (pinfunction "VDD_32") (pintype "power_in"))
      (node (ref "U7") (pin "36") (pinfunction "VDD_36") (pintype "power_in"))
      (node (ref "U7") (pin "4") (pinfunction "VDD_4") (pintype "power_in"))
      (node (ref "U7") (pin "40") (pinfunction "VDD_40") (pintype "power_in"))
      (node (ref "U7") (pin "47") (pinfunction "VDD_47") (pintype "power_in"))
      (node (ref "U7") (pin "51") (pinfunction "VDD_51") (pintype "power_in"))
      (node (ref "U7") (pin "7") (pinfunction "VDD_7") (pintype "power_in"))
      (node (ref "U8") (pin "11") (pinfunction "VDD_11") (pintype "power_in"))
      (node (ref "U8") (pin "17") (pinfunction "VDD_17") (pintype "power_in"))
      (node (ref "U8") (pin "21") (pinfunction "VDD_21") (pintype "power_in"))
      (node (ref "U8") (pin "25") (pinfunction "VDD_25") (pintype "power_in"))
      (node (ref "U8") (pin "32") (pinfunction "VDD_32") (pintype "power_in"))
      (node (ref "U8") (pin "36") (pinfunction "VDD_36") (pintype "power_in"))
      (node (ref "U8") (pin "4") (pinfunction "VDD_4") (pintype "power_in"))
      (node (ref "U8") (pin "40") (pinfunction "VDD_40") (pintype "power_in"))
      (node (ref "U8") (pin "47") (pinfunction "VDD_47") (pintype "power_in"))
      (node (ref "U8") (pin "51") (pinfunction "VDD_51") (pintype "power_in"))
      (node (ref "U8") (pin "7") (pinfunction "VDD_7") (pintype "power_in"))
      (node (ref "U9") (pin "11") (pinfunction "VDD_11") (pintype "power_in"))
      (node (ref "U9") (pin "17") (pinfunction "VDD_17") (pintype "power_in"))
      (node (ref "U9") (pin "21") (pinfunction "VDD_21") (pintype "power_in"))
      (node (ref "U9") (pin "25") (pinfunction "VDD_25") (pintype "power_in"))
      (node (ref "U9") (pin "32") (pinfunction "VDD_32") (pintype "power_in"))
      (node (ref "U9") (pin "36") (pinfunction "VDD_36") (pintype "power_in"))
      (node (ref "U9") (pin "4") (pinfunction "VDD_4") (pintype "power_in"))
      (node (ref "U9") (pin "40") (pinfunction "VDD_40") (pintype "power_in"))
      (node (ref "U9") (pin "47") (pinfunction "VDD_47") (pintype "power_in"))
      (node (ref "U9") (pin "51") (pinfunction "VDD_51") (pintype "power_in"))
      (node (ref "U9") (pin "7") (pinfunction "VDD_7") (pintype "power_in"))
    )
    (net (code "58") (name "VPLL1") (class "Default")
      (node (ref "C21") (pin "1") (pinfunction "1_1") (pintype "passive"))
      (node (ref "C23") (pin "1") (pinfunction "1_1") (pintype "passive"))
      (node (ref "C25") (pin "1") (pinfunction "1_1") (pintype "passive"))
      (node (ref "C27") (pin "1") (pinfunction "1_1") (pintype "passive"))
      (node (ref "C88") (pin "1") (pinfunction "1_1") (pintype "passive"))
      (node (ref "C90") (pin "1") (pinfunction "1_1") (pintype "passive"))
      (node (ref "C92") (pin "1") (pinfunction "1_1") (pintype "passive"))
      (node (ref "C94") (pin "1") (pinfunction "1_1") (pintype "passive"))
      (node (ref "FB1") (pin "2") (pinfunction "2_2") (pintype "passive"))
      (node (ref "FB2") (pin "2") (pinfunction "2_2") (pintype "passive"))
      (node (ref "FB3") (pin "2") (pinfunction "2_2") (pintype "passive"))
      (node (ref "FB4") (pin "2") (pinfunction "2_2") (pintype "passive"))
      (node (ref "FB5") (pin "2") (pinfunction "2_2") (pintype "passive"))
      (node (ref "FB6") (pin "2") (pinfunction "2_2") (pintype "passive"))
      (node (ref "FB7") (pin "2") (pinfunction "2_2") (pintype "passive"))
      (node (ref "FB8") (pin "2") (pinfunction "2_2") (pintype "passive"))
      (node (ref "U10") (pin "54") (pinfunction "PLL_DVDD_54") (pintype "power_in"))
      (node (ref "U3") (pin "54") (pinfunction "PLL_DVDD_54") (pintype "power_in"))
      (node (ref "U4") (pin "54") (pinfunction "PLL_DVDD_54") (pintype "power_in"))
      (node (ref "U5") (pin "54") (pinfunction "PLL_DVDD_54") (pintype "power_in"))
      (node (ref "U6") (pin "54") (pinfunction "PLL_DVDD_54") (pintype "power_in"))
      (node (ref "U7") (pin "54") (pinfunction "PLL_DVDD_54") (pintype "power_in"))
      (node (ref "U8") (pin "54") (pinfunction "PLL_DVDD_54") (pintype "power_in"))
      (node (ref "U9") (pin "54") (pinfunction "PLL_DVDD_54") (pintype "power_in"))
    )
    (net (code "59") (name "unconnected-(U3-CMODE-Pad44)") (class "Default")
      (node (ref "U3") (pin "44") (pinfunction "CMODE_44") (pintype "passive+no_connect"))
    )
    (net (code "60") (name "unconnected-(U3-RF-Pad49)") (class "Default")
      (node (ref "U3") (pin "49") (pinfunction "RF_49") (pintype "output+no_connect"))
    )
    (net (code "61") (name "unconnected-(U3-TF-Pad48)") (class "Default")
      (node (ref "U3") (pin "48") (pinfunction "TF_48") (pintype "output+no_connect"))
    )
    (net (code "62") (name "unconnected-(U4-CMODE-Pad44)") (class "Default")
      (node (ref "U4") (pin "44") (pinfunction "CMODE_44") (pintype "passive+no_connect"))
    )
    (net (code "63") (name "unconnected-(U4-RF-Pad49)") (class "Default")
      (node (ref "U4") (pin "49") (pinfunction "RF_49") (pintype "output+no_connect"))
    )
    (net (code "64") (name "unconnected-(U4-TF-Pad48)") (class "Default")
      (node (ref "U4") (pin "48") (pinfunction "TF_48") (pintype "output+no_connect"))
    )
    (net (code "65") (name "unconnected-(U4-XOUT-Pad2)") (class "Default")
      (node (ref "U4") (pin "2") (pinfunction "XOUT_2") (pintype "output+no_connect"))
    )
    (net (code "66") (name "unconnected-(U5-CMODE-Pad44)") (class "Default")
      (node (ref "U5") (pin "44") (pinfunction "CMODE_44") (pintype "passive+no_connect"))
    )
    (net (code "67") (name "unconnected-(U5-RF-Pad49)") (class "Default")
      (node (ref "U5") (pin "49") (pinfunction "RF_49") (pintype "output+no_connect"))
    )
    (net (code "68") (name "unconnected-(U5-TF-Pad48)") (class "Default")
      (node (ref "U5") (pin "48") (pinfunction "TF_48") (pintype "output+no_connect"))
    )
    (net (code "69") (name "unconnected-(U5-XOUT-Pad2)") (class "Default")
      (node (ref "U5") (pin "2") (pinfunction "XOUT_2") (pintype "output+no_connect"))
    )
    (net (code "70") (name "unconnected-(U6-CMODE-Pad44)") (class "Default")
      (node (ref "U6") (pin "44") (pinfunction "CMODE_44") (pintype "passive+no_connect"))
    )
    (net (code "71") (name "unconnected-(U6-RF-Pad49)") (class "Default")
      (node (ref "U6") (pin "49") (pinfunction "RF_49") (pintype "output+no_connect"))
    )
    (net (code "72") (name "unconnected-(U6-TF-Pad48)") (class "Default")
      (node (ref "U6") (pin "48") (pinfunction "TF_48") (pintype "output+no_connect"))
    )
    (net (code "73") (name "unconnected-(U6-XOUT-Pad2)") (class "Default")
      (node (ref "U6") (pin "2") (pinfunction "XOUT_2") (pintype "output+no_connect"))
    )
    (net (code "74") (name "unconnected-(U7-CMODE-Pad44)") (class "Default")
      (node (ref "U7") (pin "44") (pinfunction "CMODE_44") (pintype "passive+no_connect"))
    )
    (net (code "75") (name "unconnected-(U7-RF-Pad49)") (class "Default")
      (node (ref "U7") (pin "49") (pinfunction "RF_49") (pintype "output+no_connect"))
    )
    (net (code "76") (name "unconnected-(U7-TF-Pad48)") (class "Default")
      (node (ref "U7") (pin "48") (pinfunction "TF_48") (pintype "output+no_connect"))
    )
    (net (code "77") (name "unconnected-(U7-XOUT-Pad2)") (class "Default")
      (node (ref "U7") (pin "2") (pinfunction "XOUT_2") (pintype "output+no_connect"))
    )
    (net (code "78") (name "unconnected-(U8-CMODE-Pad44)") (class "Default")
      (node (ref "U8") (pin "44") (pinfunction "CMODE_44") (pintype "passive+no_connect"))
    )
    (net (code "79") (name "unconnected-(U8-RF-Pad49)") (class "Default")
      (node (ref "U8") (pin "49") (pinfunction "RF_49") (pintype "output+no_connect"))
    )
    (net (code "80") (name "unconnected-(U8-TF-Pad48)") (class "Default")
      (node (ref "U8") (pin "48") (pinfunction "TF_48") (pintype "output+no_connect"))
    )
    (net (code "81") (name "unconnected-(U8-XOUT-Pad2)") (class "Default")
      (node (ref "U8") (pin "2") (pinfunction "XOUT_2") (pintype "output+no_connect"))
    )
    (net (code "82") (name "unconnected-(U9-CMODE-Pad44)") (class "Default")
      (node (ref "U9") (pin "44") (pinfunction "CMODE_44") (pintype "passive+no_connect"))
    )
    (net (code "83") (name "unconnected-(U9-RF-Pad49)") (class "Default")
      (node (ref "U9") (pin "49") (pinfunction "RF_49") (pintype "output+no_connect"))
    )
    (net (code "84") (name "unconnected-(U9-TF-Pad48)") (class "Default")
      (node (ref "U9") (pin "48") (pinfunction "TF_48") (pintype "output+no_connect"))
    )
    (net (code "85") (name "unconnected-(U9-XOUT-Pad2)") (class "Default")
      (node (ref "U9") (pin "2") (pinfunction "XOUT_2") (pintype "output+no_connect"))
    )
    (net (code "86") (name "unconnected-(U10-CMODE-Pad44)") (class "Default")
      (node (ref "U10") (pin "44") (pinfunction "CMODE_44") (pintype "passive+no_connect"))
    )
    (net (code "87") (name "unconnected-(U10-RF-Pad49)") (class "Default")
      (node (ref "U10") (pin "49") (pinfunction "RF_49") (pintype "output+no_connect"))
    )
    (net (code "88") (name "unconnected-(U10-TF-Pad48)") (class "Default")
      (node (ref "U10") (pin "48") (pinfunction "TF_48") (pintype "output+no_connect"))
    )
    (net (code "89") (name "unconnected-(U10-XOUT-Pad2)") (class "Default")
      (node (ref "U10") (pin "2") (pinfunction "XOUT_2") (pintype "output+no_connect"))
    )
  )
)
